# DNVT_box3t.net
KiCad netlist of a schematic drawn in EAGLE
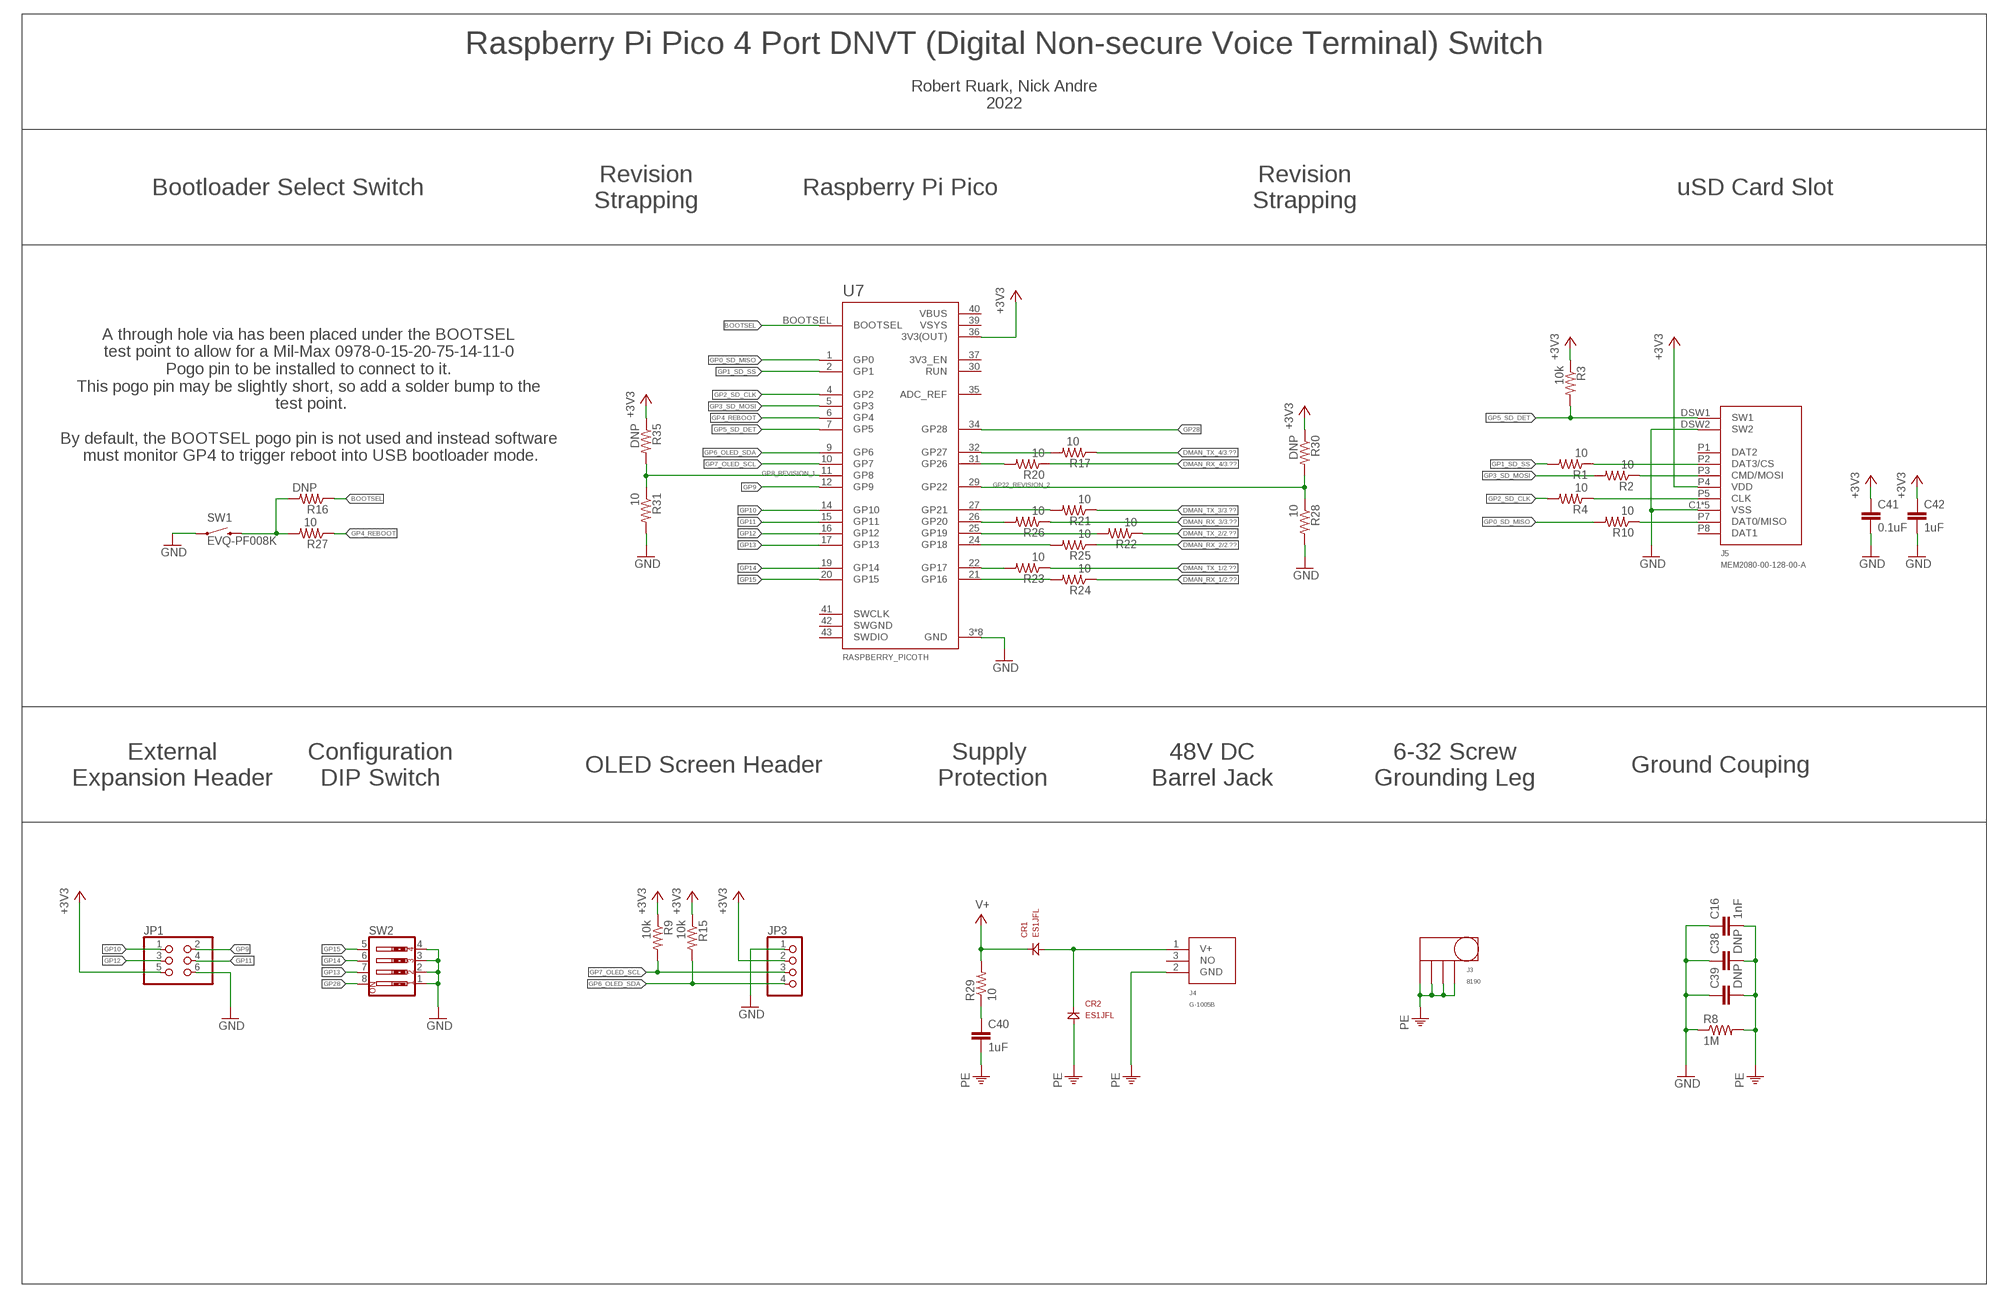
[diagram p0: schematic, sheet 1]
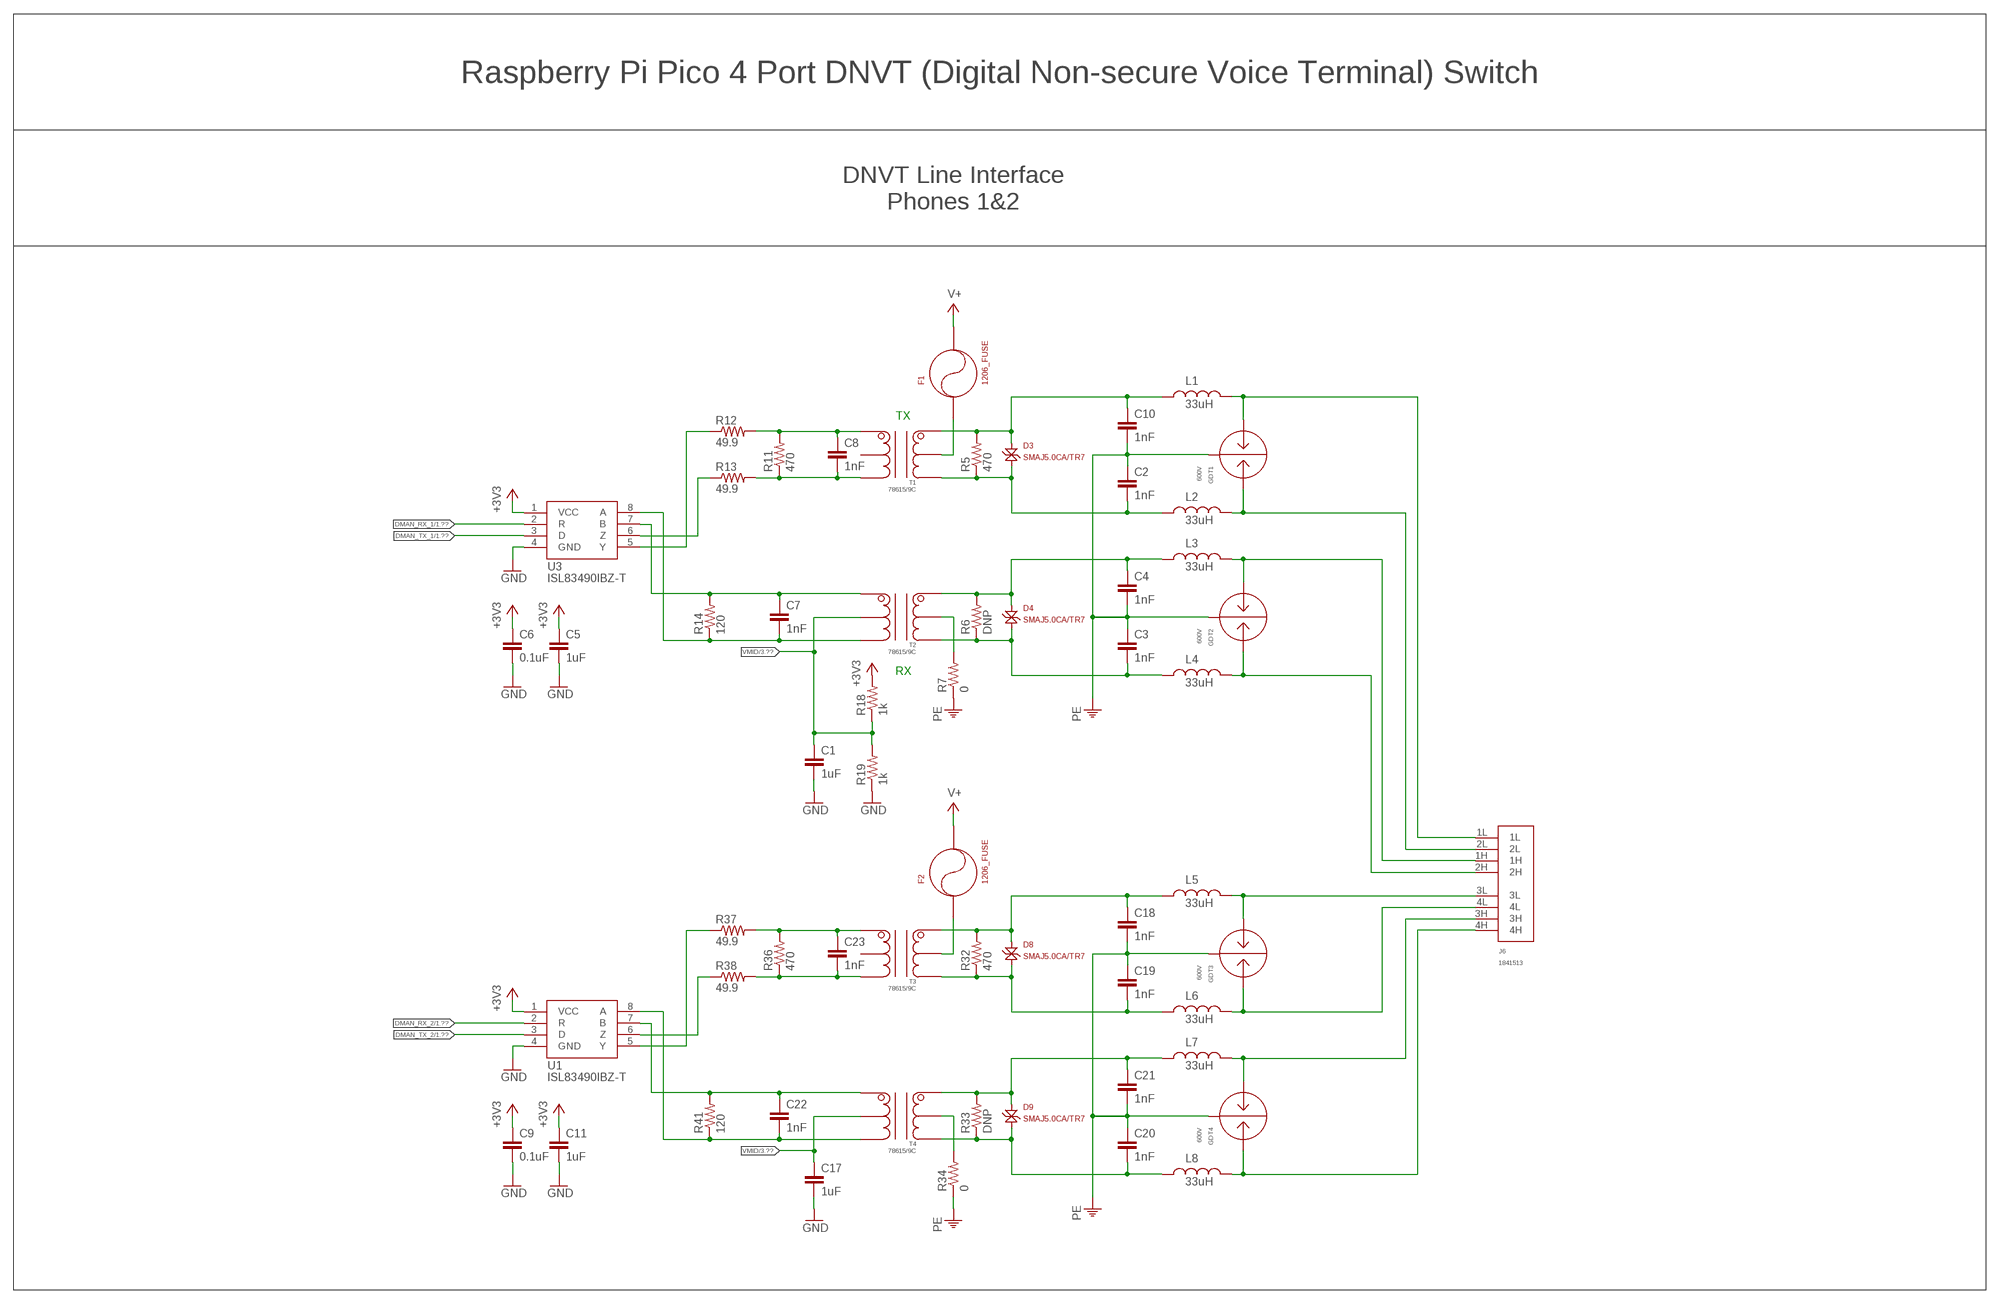
[diagram p1: schematic, sheet 2]
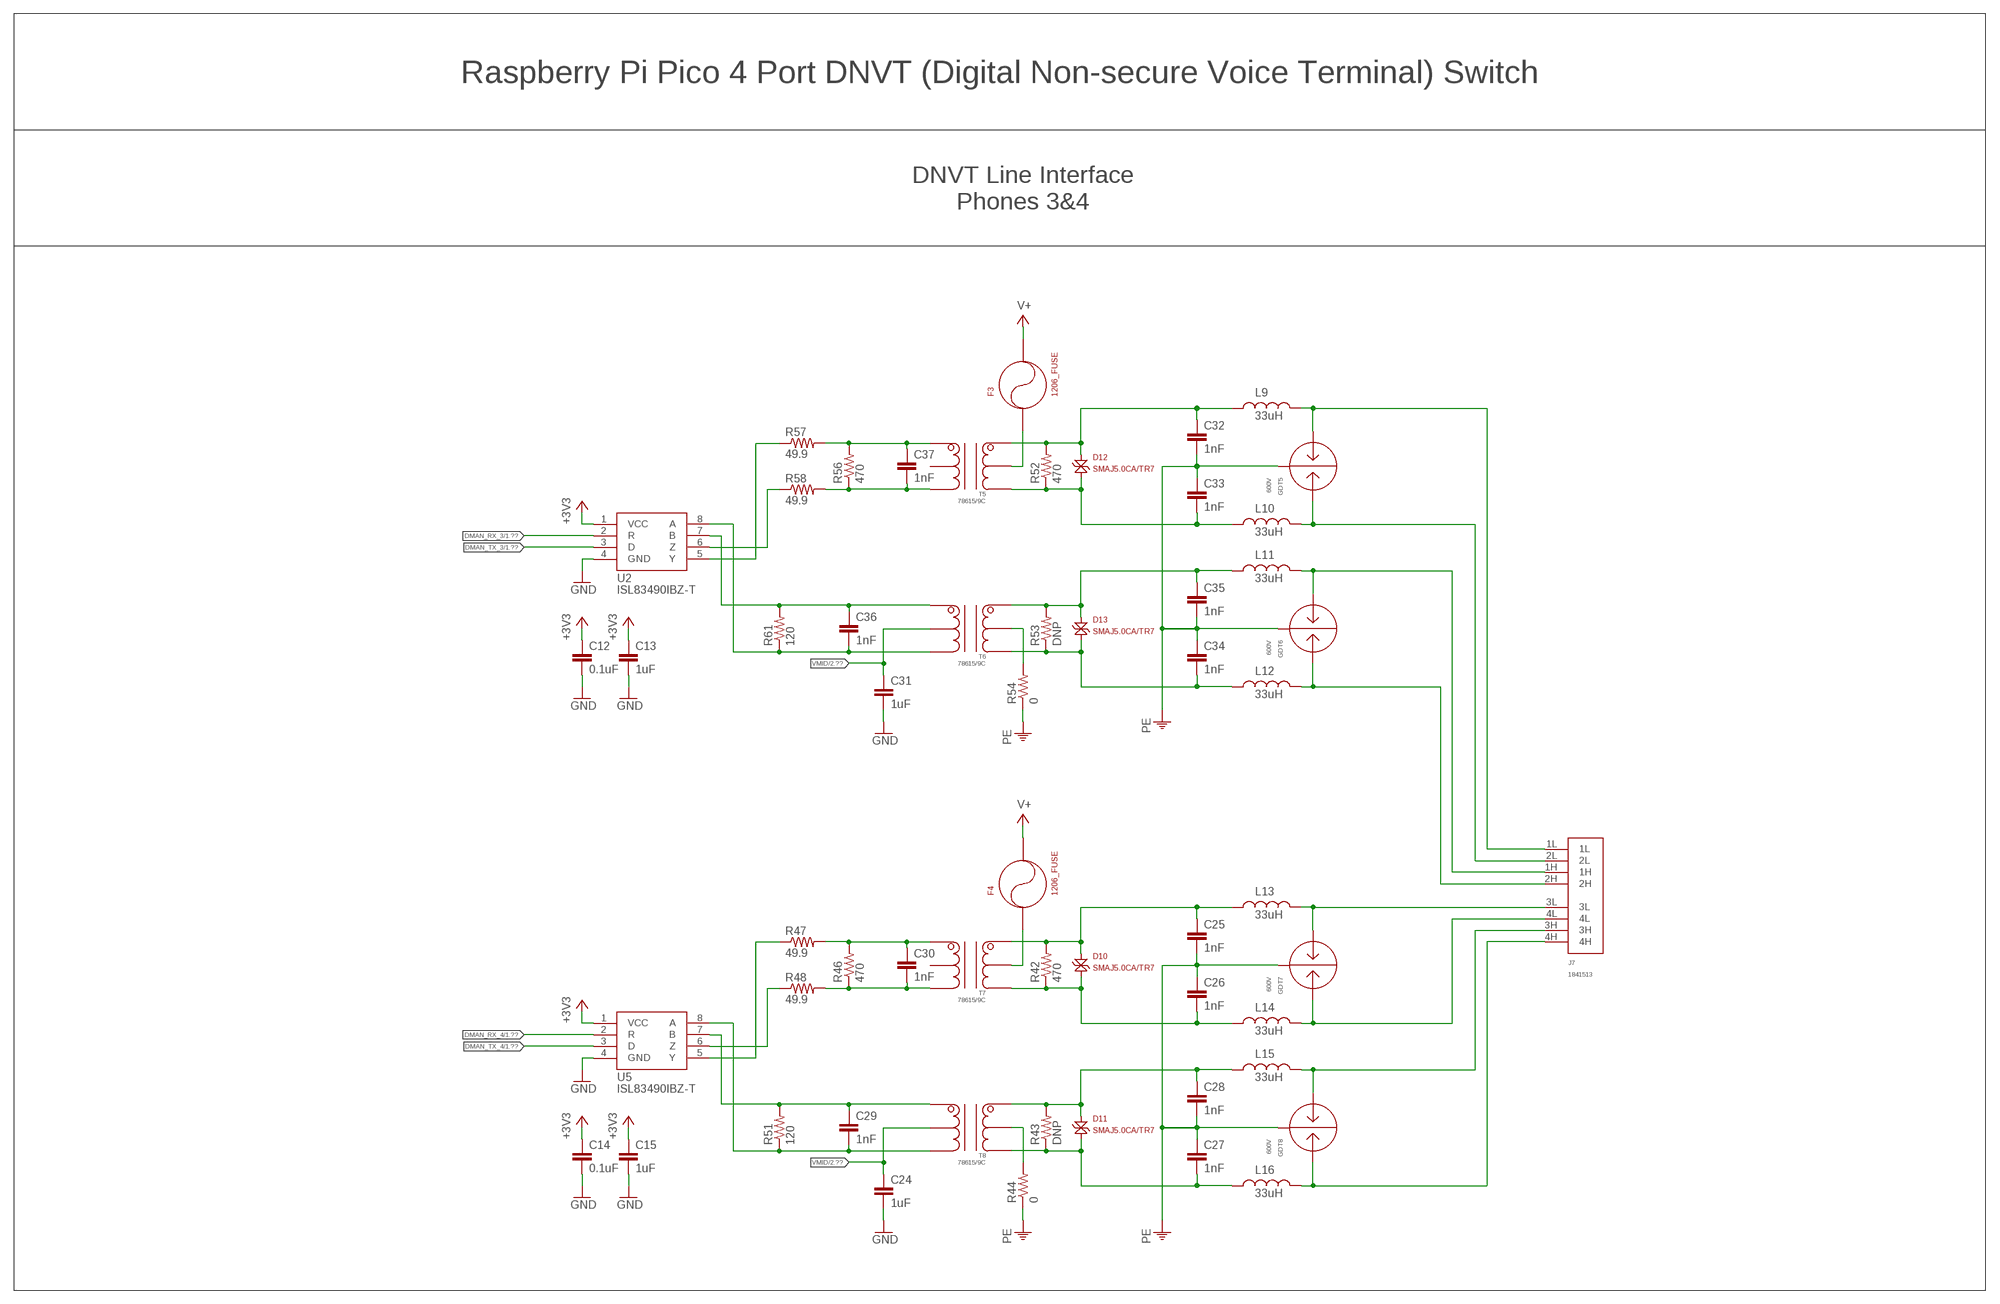
[diagram p2: schematic, sheet 3]

(export (version "E")
  (design (tool "Eeschema 10.0.6"))
  (components
    (comp (ref "C1")
      (value "1uF")
      (footprint "eagle-import:0805")
      (libsource (lib "eagle-import") (part "0805_CAPACITOR"))
    )
    (comp (ref "C2")
      (value "1nF")
      (footprint "eagle-import:0805")
      (libsource (lib "eagle-import") (part "0805_CAPACITOR"))
    )
    (comp (ref "C3")
      (value "1nF")
      (footprint "eagle-import:0805")
      (libsource (lib "eagle-import") (part "0805_CAPACITOR"))
    )
    (comp (ref "C4")
      (value "1nF")
      (footprint "eagle-import:0805")
      (libsource (lib "eagle-import") (part "0805_CAPACITOR"))
    )
    (comp (ref "C5")
      (value "1uF")
      (footprint "eagle-import:0805")
      (libsource (lib "eagle-import") (part "0805_CAPACITOR"))
    )
    (comp (ref "C6")
      (value "0.1uF")
      (footprint "eagle-import:0603")
      (libsource (lib "eagle-import") (part "0603_CAPACITOR"))
    )
    (comp (ref "C7")
      (value "1nF")
      (footprint "eagle-import:0805")
      (libsource (lib "eagle-import") (part "0805_CAPACITOR"))
    )
    (comp (ref "C8")
      (value "1nF")
      (footprint "eagle-import:0805")
      (libsource (lib "eagle-import") (part "0805_CAPACITOR"))
    )
    (comp (ref "C9")
      (value "0.1uF")
      (footprint "eagle-import:0603")
      (libsource (lib "eagle-import") (part "0603_CAPACITOR"))
    )
    (comp (ref "C10")
      (value "1nF")
      (footprint "eagle-import:0805")
      (libsource (lib "eagle-import") (part "0805_CAPACITOR"))
    )
    (comp (ref "C11")
      (value "1uF")
      (footprint "eagle-import:0805")
      (libsource (lib "eagle-import") (part "0805_CAPACITOR"))
    )
    (comp (ref "C17")
      (value "1uF")
      (footprint "eagle-import:0805")
      (libsource (lib "eagle-import") (part "0805_CAPACITOR"))
    )
    (comp (ref "C18")
      (value "1nF")
      (footprint "eagle-import:0805")
      (libsource (lib "eagle-import") (part "0805_CAPACITOR"))
    )
    (comp (ref "C19")
      (value "1nF")
      (footprint "eagle-import:0805")
      (libsource (lib "eagle-import") (part "0805_CAPACITOR"))
    )
    (comp (ref "C20")
      (value "1nF")
      (footprint "eagle-import:0805")
      (libsource (lib "eagle-import") (part "0805_CAPACITOR"))
    )
    (comp (ref "C21")
      (value "1nF")
      (footprint "eagle-import:0805")
      (libsource (lib "eagle-import") (part "0805_CAPACITOR"))
    )
    (comp (ref "C22")
      (value "1nF")
      (footprint "eagle-import:0805")
      (libsource (lib "eagle-import") (part "0805_CAPACITOR"))
    )
    (comp (ref "C23")
      (value "1nF")
      (footprint "eagle-import:0805")
      (libsource (lib "eagle-import") (part "0805_CAPACITOR"))
    )
    (comp (ref "D3")
      (value "SMAJ5.0CA/TR7")
      (footprint "eagle-import:DO-214AC_NO_POL")
      (libsource (lib "eagle-import") (part "SMAJ5.0CA/TR7"))
    )
    (comp (ref "D4")
      (value "SMAJ5.0CA/TR7")
      (footprint "eagle-import:DO-214AC_NO_POL")
      (libsource (lib "eagle-import") (part "SMAJ5.0CA/TR7"))
    )
    (comp (ref "D8")
      (value "SMAJ5.0CA/TR7")
      (footprint "eagle-import:DO-214AC_NO_POL")
      (libsource (lib "eagle-import") (part "SMAJ5.0CA/TR7"))
    )
    (comp (ref "D9")
      (value "SMAJ5.0CA/TR7")
      (footprint "eagle-import:DO-214AC_NO_POL")
      (libsource (lib "eagle-import") (part "SMAJ5.0CA/TR7"))
    )
    (comp (ref "F1")
      (value "1206_FUSE")
      (footprint "eagle-import:1206")
      (libsource (lib "eagle-import") (part "1206_FUSE"))
    )
    (comp (ref "F2")
      (value "1206_FUSE")
      (footprint "eagle-import:1206")
      (libsource (lib "eagle-import") (part "1206_FUSE"))
    )
    (comp (ref "GDT1")
      (value "600V")
      (footprint "eagle-import:2036_GDT")
      (fields (field (name "PARTNO") "2036-60-SM-RPLFCT-ND"))
      (libsource (lib "eagle-import") (part "2036-60-SM-RPLF"))
    )
    (comp (ref "GDT2")
      (value "600V")
      (footprint "eagle-import:2036_GDT")
      (fields (field (name "PARTNO") "2036-60-SM-RPLFCT-ND"))
      (libsource (lib "eagle-import") (part "2036-60-SM-RPLF"))
    )
    (comp (ref "GDT3")
      (value "600V")
      (footprint "eagle-import:2036_GDT")
      (fields (field (name "PARTNO") "2036-60-SM-RPLFCT-ND"))
      (libsource (lib "eagle-import") (part "2036-60-SM-RPLF"))
    )
    (comp (ref "GDT4")
      (value "600V")
      (footprint "eagle-import:2036_GDT")
      (fields (field (name "PARTNO") "2036-60-SM-RPLFCT-ND"))
      (libsource (lib "eagle-import") (part "2036-60-SM-RPLF"))
    )
    (comp (ref "J6")
      (value "1841513")
      (footprint "eagle-import:1841513")
      (fields (field (name "PARTNO") "277-10317-ND"))
      (libsource (lib "eagle-import") (part "1841513"))
    )
    (comp (ref "L1")
      (value "33uH")
      (footprint "eagle-import:SDR0403")
      (fields (field (name "PARTNO") "SDR0403-330KLCT-ND"))
      (libsource (lib "eagle-import") (part "SDR0403-330KL"))
    )
    (comp (ref "L2")
      (value "33uH")
      (footprint "eagle-import:SDR0403")
      (fields (field (name "PARTNO") "SDR0403-330KLCT-ND"))
      (libsource (lib "eagle-import") (part "SDR0403-330KL"))
    )
    (comp (ref "L3")
      (value "33uH")
      (footprint "eagle-import:SDR0403")
      (fields (field (name "PARTNO") "SDR0403-330KLCT-ND"))
      (libsource (lib "eagle-import") (part "SDR0403-330KL"))
    )
    (comp (ref "L4")
      (value "33uH")
      (footprint "eagle-import:SDR0403")
      (fields (field (name "PARTNO") "SDR0403-330KLCT-ND"))
      (libsource (lib "eagle-import") (part "SDR0403-330KL"))
    )
    (comp (ref "L5")
      (value "33uH")
      (footprint "eagle-import:SDR0403")
      (fields (field (name "PARTNO") "SDR0403-330KLCT-ND"))
      (libsource (lib "eagle-import") (part "SDR0403-330KL"))
    )
    (comp (ref "L6")
      (value "33uH")
      (footprint "eagle-import:SDR0403")
      (fields (field (name "PARTNO") "SDR0403-330KLCT-ND"))
      (libsource (lib "eagle-import") (part "SDR0403-330KL"))
    )
    (comp (ref "L7")
      (value "33uH")
      (footprint "eagle-import:SDR0403")
      (fields (field (name "PARTNO") "SDR0403-330KLCT-ND"))
      (libsource (lib "eagle-import") (part "SDR0403-330KL"))
    )
    (comp (ref "L8")
      (value "33uH")
      (footprint "eagle-import:SDR0403")
      (fields (field (name "PARTNO") "SDR0403-330KLCT-ND"))
      (libsource (lib "eagle-import") (part "SDR0403-330KL"))
    )
    (comp (ref "R5")
      (value "470")
      (footprint "eagle-import:R0805")
      (libsource (lib "eagle-import") (part "R-US_R0805"))
    )
    (comp (ref "R6")
      (value "DNP")
      (footprint "eagle-import:R0805")
      (libsource (lib "eagle-import") (part "R-US_R0805"))
    )
    (comp (ref "R7")
      (value "0")
      (footprint "eagle-import:R0805")
      (libsource (lib "eagle-import") (part "R-US_R0805"))
    )
    (comp (ref "R11")
      (value "470")
      (footprint "eagle-import:R0805")
      (libsource (lib "eagle-import") (part "R-US_R0805"))
    )
    (comp (ref "R12")
      (value "49.9")
      (footprint "eagle-import:R0805")
      (libsource (lib "eagle-import") (part "R-US_R0805"))
    )
    (comp (ref "R13")
      (value "49.9")
      (footprint "eagle-import:R0805")
      (libsource (lib "eagle-import") (part "R-US_R0805"))
    )
    (comp (ref "R14")
      (value "120")
      (footprint "eagle-import:1206")
      (libsource (lib "eagle-import") (part "1206_RESISTOR"))
    )
    (comp (ref "R18")
      (value "1k")
      (footprint "eagle-import:0603")
      (libsource (lib "eagle-import") (part "0603_RESISTOR"))
    )
    (comp (ref "R19")
      (value "1k")
      (footprint "eagle-import:0603")
      (libsource (lib "eagle-import") (part "0603_RESISTOR"))
    )
    (comp (ref "R32")
      (value "470")
      (footprint "eagle-import:R0805")
      (libsource (lib "eagle-import") (part "R-US_R0805"))
    )
    (comp (ref "R33")
      (value "DNP")
      (footprint "eagle-import:R0805")
      (libsource (lib "eagle-import") (part "R-US_R0805"))
    )
    (comp (ref "R34")
      (value "0")
      (footprint "eagle-import:R0805")
      (libsource (lib "eagle-import") (part "R-US_R0805"))
    )
    (comp (ref "R36")
      (value "470")
      (footprint "eagle-import:R0805")
      (libsource (lib "eagle-import") (part "R-US_R0805"))
    )
    (comp (ref "R37")
      (value "49.9")
      (footprint "eagle-import:R0805")
      (libsource (lib "eagle-import") (part "R-US_R0805"))
    )
    (comp (ref "R38")
      (value "49.9")
      (footprint "eagle-import:R0805")
      (libsource (lib "eagle-import") (part "R-US_R0805"))
    )
    (comp (ref "R41")
      (value "120")
      (footprint "eagle-import:1206")
      (libsource (lib "eagle-import") (part "1206_RESISTOR"))
    )
    (comp (ref "T1")
      (value "78615/9C")
      (footprint "eagle-import:786T")
      (libsource (lib "eagle-import") (part "78615/9C"))
    )
    (comp (ref "T2")
      (value "78615/9C")
      (footprint "eagle-import:786T")
      (libsource (lib "eagle-import") (part "78615/9C"))
    )
    (comp (ref "T3")
      (value "78615/9C")
      (footprint "eagle-import:786T")
      (libsource (lib "eagle-import") (part "78615/9C"))
    )
    (comp (ref "T4")
      (value "78615/9C")
      (footprint "eagle-import:786T")
      (libsource (lib "eagle-import") (part "78615/9C"))
    )
    (comp (ref "U1")
      (value "ISL83490IBZ-T")
      (footprint "eagle-import:SOIC8")
      (fields (field (name "PARTNO") "ISL83490IBZ-TCT-ND"))
      (libsource (lib "eagle-import") (part "ISL83490IBZ-T"))
    )
    (comp (ref "U3")
      (value "ISL83490IBZ-T")
      (footprint "eagle-import:SOIC8")
      (fields (field (name "PARTNO") "ISL83490IBZ-TCT-ND"))
      (libsource (lib "eagle-import") (part "ISL83490IBZ-T"))
    )
    (comp (ref "C12")
      (value "0.1uF")
      (footprint "eagle-import:0603")
      (libsource (lib "eagle-import") (part "0603_CAPACITOR"))
    )
    (comp (ref "C13")
      (value "1uF")
      (footprint "eagle-import:0805")
      (libsource (lib "eagle-import") (part "0805_CAPACITOR"))
    )
    (comp (ref "C14")
      (value "0.1uF")
      (footprint "eagle-import:0603")
      (libsource (lib "eagle-import") (part "0603_CAPACITOR"))
    )
    (comp (ref "C15")
      (value "1uF")
      (footprint "eagle-import:0805")
      (libsource (lib "eagle-import") (part "0805_CAPACITOR"))
    )
    (comp (ref "C24")
      (value "1uF")
      (footprint "eagle-import:0805")
      (libsource (lib "eagle-import") (part "0805_CAPACITOR"))
    )
    (comp (ref "C25")
      (value "1nF")
      (footprint "eagle-import:0805")
      (libsource (lib "eagle-import") (part "0805_CAPACITOR"))
    )
    (comp (ref "C26")
      (value "1nF")
      (footprint "eagle-import:0805")
      (libsource (lib "eagle-import") (part "0805_CAPACITOR"))
    )
    (comp (ref "C27")
      (value "1nF")
      (footprint "eagle-import:0805")
      (libsource (lib "eagle-import") (part "0805_CAPACITOR"))
    )
    (comp (ref "C28")
      (value "1nF")
      (footprint "eagle-import:0805")
      (libsource (lib "eagle-import") (part "0805_CAPACITOR"))
    )
    (comp (ref "C29")
      (value "1nF")
      (footprint "eagle-import:0805")
      (libsource (lib "eagle-import") (part "0805_CAPACITOR"))
    )
    (comp (ref "C30")
      (value "1nF")
      (footprint "eagle-import:0805")
      (libsource (lib "eagle-import") (part "0805_CAPACITOR"))
    )
    (comp (ref "C31")
      (value "1uF")
      (footprint "eagle-import:0805")
      (libsource (lib "eagle-import") (part "0805_CAPACITOR"))
    )
    (comp (ref "C32")
      (value "1nF")
      (footprint "eagle-import:0805")
      (libsource (lib "eagle-import") (part "0805_CAPACITOR"))
    )
    (comp (ref "C33")
      (value "1nF")
      (footprint "eagle-import:0805")
      (libsource (lib "eagle-import") (part "0805_CAPACITOR"))
    )
    (comp (ref "C34")
      (value "1nF")
      (footprint "eagle-import:0805")
      (libsource (lib "eagle-import") (part "0805_CAPACITOR"))
    )
    (comp (ref "C35")
      (value "1nF")
      (footprint "eagle-import:0805")
      (libsource (lib "eagle-import") (part "0805_CAPACITOR"))
    )
    (comp (ref "C36")
      (value "1nF")
      (footprint "eagle-import:0805")
      (libsource (lib "eagle-import") (part "0805_CAPACITOR"))
    )
    (comp (ref "C37")
      (value "1nF")
      (footprint "eagle-import:0805")
      (libsource (lib "eagle-import") (part "0805_CAPACITOR"))
    )
    (comp (ref "D10")
      (value "SMAJ5.0CA/TR7")
      (footprint "eagle-import:DO-214AC_NO_POL")
      (libsource (lib "eagle-import") (part "SMAJ5.0CA/TR7"))
    )
    (comp (ref "D11")
      (value "SMAJ5.0CA/TR7")
      (footprint "eagle-import:DO-214AC_NO_POL")
      (libsource (lib "eagle-import") (part "SMAJ5.0CA/TR7"))
    )
    (comp (ref "D12")
      (value "SMAJ5.0CA/TR7")
      (footprint "eagle-import:DO-214AC_NO_POL")
      (libsource (lib "eagle-import") (part "SMAJ5.0CA/TR7"))
    )
    (comp (ref "D13")
      (value "SMAJ5.0CA/TR7")
      (footprint "eagle-import:DO-214AC_NO_POL")
      (libsource (lib "eagle-import") (part "SMAJ5.0CA/TR7"))
    )
    (comp (ref "F3")
      (value "1206_FUSE")
      (footprint "eagle-import:1206")
      (libsource (lib "eagle-import") (part "1206_FUSE"))
    )
    (comp (ref "F4")
      (value "1206_FUSE")
      (footprint "eagle-import:1206")
      (libsource (lib "eagle-import") (part "1206_FUSE"))
    )
    (comp (ref "GDT5")
      (value "600V")
      (footprint "eagle-import:2036_GDT")
      (fields (field (name "PARTNO") "2036-60-SM-RPLFCT-ND"))
      (libsource (lib "eagle-import") (part "2036-60-SM-RPLF"))
    )
    (comp (ref "GDT6")
      (value "600V")
      (footprint "eagle-import:2036_GDT")
      (fields (field (name "PARTNO") "2036-60-SM-RPLFCT-ND"))
      (libsource (lib "eagle-import") (part "2036-60-SM-RPLF"))
    )
    (comp (ref "GDT7")
      (value "600V")
      (footprint "eagle-import:2036_GDT")
      (fields (field (name "PARTNO") "2036-60-SM-RPLFCT-ND"))
      (libsource (lib "eagle-import") (part "2036-60-SM-RPLF"))
    )
    (comp (ref "GDT8")
      (value "600V")
      (footprint "eagle-import:2036_GDT")
      (fields (field (name "PARTNO") "2036-60-SM-RPLFCT-ND"))
      (libsource (lib "eagle-import") (part "2036-60-SM-RPLF"))
    )
    (comp (ref "J7")
      (value "1841513")
      (footprint "eagle-import:1841513")
      (fields (field (name "PARTNO") "277-10317-ND"))
      (libsource (lib "eagle-import") (part "1841513"))
    )
    (comp (ref "L9")
      (value "33uH")
      (footprint "eagle-import:SDR0403")
      (fields (field (name "PARTNO") "SDR0403-330KLCT-ND"))
      (libsource (lib "eagle-import") (part "SDR0403-330KL"))
    )
    (comp (ref "L10")
      (value "33uH")
      (footprint "eagle-import:SDR0403")
      (fields (field (name "PARTNO") "SDR0403-330KLCT-ND"))
      (libsource (lib "eagle-import") (part "SDR0403-330KL"))
    )
    (comp (ref "L11")
      (value "33uH")
      (footprint "eagle-import:SDR0403")
      (fields (field (name "PARTNO") "SDR0403-330KLCT-ND"))
      (libsource (lib "eagle-import") (part "SDR0403-330KL"))
    )
    (comp (ref "L12")
      (value "33uH")
      (footprint "eagle-import:SDR0403")
      (fields (field (name "PARTNO") "SDR0403-330KLCT-ND"))
      (libsource (lib "eagle-import") (part "SDR0403-330KL"))
    )
    (comp (ref "L13")
      (value "33uH")
      (footprint "eagle-import:SDR0403")
      (fields (field (name "PARTNO") "SDR0403-330KLCT-ND"))
      (libsource (lib "eagle-import") (part "SDR0403-330KL"))
    )
    (comp (ref "L14")
      (value "33uH")
      (footprint "eagle-import:SDR0403")
      (fields (field (name "PARTNO") "SDR0403-330KLCT-ND"))
      (libsource (lib "eagle-import") (part "SDR0403-330KL"))
    )
    (comp (ref "L15")
      (value "33uH")
      (footprint "eagle-import:SDR0403")
      (fields (field (name "PARTNO") "SDR0403-330KLCT-ND"))
      (libsource (lib "eagle-import") (part "SDR0403-330KL"))
    )
    (comp (ref "L16")
      (value "33uH")
      (footprint "eagle-import:SDR0403")
      (fields (field (name "PARTNO") "SDR0403-330KLCT-ND"))
      (libsource (lib "eagle-import") (part "SDR0403-330KL"))
    )
    (comp (ref "R42")
      (value "470")
      (footprint "eagle-import:R0805")
      (libsource (lib "eagle-import") (part "R-US_R0805"))
    )
    (comp (ref "R43")
      (value "DNP")
      (footprint "eagle-import:R0805")
      (libsource (lib "eagle-import") (part "R-US_R0805"))
    )
    (comp (ref "R44")
      (value "0")
      (footprint "eagle-import:R0805")
      (libsource (lib "eagle-import") (part "R-US_R0805"))
    )
    (comp (ref "R46")
      (value "470")
      (footprint "eagle-import:R0805")
      (libsource (lib "eagle-import") (part "R-US_R0805"))
    )
    (comp (ref "R47")
      (value "49.9")
      (footprint "eagle-import:R0805")
      (libsource (lib "eagle-import") (part "R-US_R0805"))
    )
    (comp (ref "R48")
      (value "49.9")
      (footprint "eagle-import:R0805")
      (libsource (lib "eagle-import") (part "R-US_R0805"))
    )
    (comp (ref "R51")
      (value "120")
      (footprint "eagle-import:1206")
      (libsource (lib "eagle-import") (part "1206_RESISTOR"))
    )
    (comp (ref "R52")
      (value "470")
      (footprint "eagle-import:R0805")
      (libsource (lib "eagle-import") (part "R-US_R0805"))
    )
    (comp (ref "R53")
      (value "DNP")
      (footprint "eagle-import:R0805")
      (libsource (lib "eagle-import") (part "R-US_R0805"))
    )
    (comp (ref "R54")
      (value "0")
      (footprint "eagle-import:R0805")
      (libsource (lib "eagle-import") (part "R-US_R0805"))
    )
    (comp (ref "R56")
      (value "470")
      (footprint "eagle-import:R0805")
      (libsource (lib "eagle-import") (part "R-US_R0805"))
    )
    (comp (ref "R57")
      (value "49.9")
      (footprint "eagle-import:R0805")
      (libsource (lib "eagle-import") (part "R-US_R0805"))
    )
    (comp (ref "R58")
      (value "49.9")
      (footprint "eagle-import:R0805")
      (libsource (lib "eagle-import") (part "R-US_R0805"))
    )
    (comp (ref "R61")
      (value "120")
      (footprint "eagle-import:1206")
      (libsource (lib "eagle-import") (part "1206_RESISTOR"))
    )
    (comp (ref "T5")
      (value "78615/9C")
      (footprint "eagle-import:786T")
      (libsource (lib "eagle-import") (part "78615/9C"))
    )
    (comp (ref "T6")
      (value "78615/9C")
      (footprint "eagle-import:786T")
      (libsource (lib "eagle-import") (part "78615/9C"))
    )
    (comp (ref "T7")
      (value "78615/9C")
      (footprint "eagle-import:786T")
      (libsource (lib "eagle-import") (part "78615/9C"))
    )
    (comp (ref "T8")
      (value "78615/9C")
      (footprint "eagle-import:786T")
      (libsource (lib "eagle-import") (part "78615/9C"))
    )
    (comp (ref "U2")
      (value "ISL83490IBZ-T")
      (footprint "eagle-import:SOIC8")
      (fields (field (name "PARTNO") "ISL83490IBZ-TCT-ND"))
      (libsource (lib "eagle-import") (part "ISL83490IBZ-T"))
    )
    (comp (ref "U5")
      (value "ISL83490IBZ-T")
      (footprint "eagle-import:SOIC8")
      (fields (field (name "PARTNO") "ISL83490IBZ-TCT-ND"))
      (libsource (lib "eagle-import") (part "ISL83490IBZ-T"))
    )
    (comp (ref "C16")
      (value "1nF")
      (footprint "eagle-import:1206")
      (libsource (lib "eagle-import") (part "1206_CAPACITOR"))
    )
    (comp (ref "C38")
      (value "DNP")
      (footprint "eagle-import:1206")
      (libsource (lib "eagle-import") (part "1206_CAPACITOR"))
    )
    (comp (ref "C39")
      (value "DNP")
      (footprint "eagle-import:1206")
      (libsource (lib "eagle-import") (part "1206_CAPACITOR"))
    )
    (comp (ref "C40")
      (value "1uF")
      (footprint "eagle-import:1206")
      (libsource (lib "eagle-import") (part "1206_CAPACITOR"))
    )
    (comp (ref "C41")
      (value "0.1uF")
      (footprint "eagle-import:0603")
      (libsource (lib "eagle-import") (part "0603_CAPACITOR"))
    )
    (comp (ref "C42")
      (value "1uF")
      (footprint "eagle-import:0805")
      (libsource (lib "eagle-import") (part "0805_CAPACITOR"))
    )
    (comp (ref "CR1")
      (value "ES1JFL")
      (footprint "eagle-import:SOD123(AK)")
      (fields (field (name "PARTNO") "ES1JFLCT-ND"))
      (libsource (lib "eagle-import") (part "ES1JFL"))
    )
    (comp (ref "CR2")
      (value "ES1JFL")
      (footprint "eagle-import:SOD123(AK)")
      (fields (field (name "PARTNO") "ES1JFLCT-ND"))
      (libsource (lib "eagle-import") (part "ES1JFL"))
    )
    (comp (ref "J3")
      (value "8190")
      (footprint "eagle-import:7781")
      (fields (field (name "PARTNO") "36-8190-ND"))
      (libsource (lib "eagle-import") (part "8190"))
    )
    (comp (ref "J4")
      (value "G-1005B")
      (footprint "eagle-import:G-1005B")
      (fields (field (name "PARTNO") "1939-G-1005B-ND"))
      (libsource (lib "eagle-import") (part "G-1005B"))
    )
    (comp (ref "J5")
      (value "MEM2080-00-128-00-A")
      (footprint "eagle-import:MEM2080")
      (fields (field (name "PARTNO") "2073-MEM2080-00-128-00-ACT-ND"))
      (libsource (lib "eagle-import") (part "MEM2080-00-128-00-A"))
    )
    (comp (ref "JP1")
      (value "PINHD-2X3/90")
      (footprint "eagle-import:2X03_90")
      (libsource (lib "eagle-import") (part "PINHD-2X3/90"))
    )
    (comp (ref "JP3")
      (value "PINHD-1X4")
      (footprint "eagle-import:1X04")
      (libsource (lib "eagle-import") (part "PINHD-1X4"))
    )
    (comp (ref "R1")
      (value "10")
      (footprint "eagle-import:0603")
      (libsource (lib "eagle-import") (part "0603_RESISTOR"))
    )
    (comp (ref "R2")
      (value "10")
      (footprint "eagle-import:0603")
      (libsource (lib "eagle-import") (part "0603_RESISTOR"))
    )
    (comp (ref "R3")
      (value "10k")
      (footprint "eagle-import:0603")
      (libsource (lib "eagle-import") (part "0603_RESISTOR"))
    )
    (comp (ref "R4")
      (value "10")
      (footprint "eagle-import:0603")
      (libsource (lib "eagle-import") (part "0603_RESISTOR"))
    )
    (comp (ref "R8")
      (value "1M")
      (footprint "eagle-import:1206")
      (libsource (lib "eagle-import") (part "1206_RESISTOR"))
    )
    (comp (ref "R9")
      (value "10k")
      (footprint "eagle-import:0603")
      (libsource (lib "eagle-import") (part "0603_RESISTOR"))
    )
    (comp (ref "R10")
      (value "10")
      (footprint "eagle-import:0603")
      (libsource (lib "eagle-import") (part "0603_RESISTOR"))
    )
    (comp (ref "R15")
      (value "10k")
      (footprint "eagle-import:0603")
      (libsource (lib "eagle-import") (part "0603_RESISTOR"))
    )
    (comp (ref "R16")
      (value "DNP")
      (footprint "eagle-import:0603")
      (libsource (lib "eagle-import") (part "0603_RESISTOR"))
    )
    (comp (ref "R17")
      (value "10")
      (footprint "eagle-import:0603")
      (libsource (lib "eagle-import") (part "0603_RESISTOR"))
    )
    (comp (ref "R20")
      (value "10")
      (footprint "eagle-import:0603")
      (libsource (lib "eagle-import") (part "0603_RESISTOR"))
    )
    (comp (ref "R21")
      (value "10")
      (footprint "eagle-import:0603")
      (libsource (lib "eagle-import") (part "0603_RESISTOR"))
    )
    (comp (ref "R22")
      (value "10")
      (footprint "eagle-import:0603")
      (libsource (lib "eagle-import") (part "0603_RESISTOR"))
    )
    (comp (ref "R23")
      (value "10")
      (footprint "eagle-import:0603")
      (libsource (lib "eagle-import") (part "0603_RESISTOR"))
    )
    (comp (ref "R24")
      (value "10")
      (footprint "eagle-import:0603")
      (libsource (lib "eagle-import") (part "0603_RESISTOR"))
    )
    (comp (ref "R25")
      (value "10")
      (footprint "eagle-import:0603")
      (libsource (lib "eagle-import") (part "0603_RESISTOR"))
    )
    (comp (ref "R26")
      (value "10")
      (footprint "eagle-import:0603")
      (libsource (lib "eagle-import") (part "0603_RESISTOR"))
    )
    (comp (ref "R27")
      (value "10")
      (footprint "eagle-import:0603")
      (libsource (lib "eagle-import") (part "0603_RESISTOR"))
    )
    (comp (ref "R28")
      (value "10")
      (footprint "eagle-import:0603")
      (libsource (lib "eagle-import") (part "0603_RESISTOR"))
    )
    (comp (ref "R29")
      (value "10")
      (footprint "eagle-import:1206")
      (libsource (lib "eagle-import") (part "1206_RESISTOR"))
    )
    (comp (ref "R30")
      (value "DNP")
      (footprint "eagle-import:0603")
      (libsource (lib "eagle-import") (part "0603_RESISTOR"))
    )
    (comp (ref "R31")
      (value "10")
      (footprint "eagle-import:0603")
      (libsource (lib "eagle-import") (part "0603_RESISTOR"))
    )
    (comp (ref "R35")
      (value "DNP")
      (footprint "eagle-import:0603")
      (libsource (lib "eagle-import") (part "0603_RESISTOR"))
    )
    (comp (ref "SW1")
      (value "EVQ-PF008K")
      (footprint "eagle-import:EVQ-PF008K")
      (fields (field (name "PARTNO") "P10880S-ND"))
      (libsource (lib "eagle-import") (part "EVQ-PF008K"))
    )
    (comp (ref "SW2")
      (value "SW_DIP-4")
      (footprint "eagle-import:EDG-04")
      (libsource (lib "eagle-import") (part "SW_DIP-4"))
    )
    (comp (ref "U7")
      (value "RASPBERRY_PICOTH")
      (footprint "eagle-import:PICO-PKG-TH")
      (libsource (lib "eagle-import") (part "RASPBERRY_PICOTH"))
    )
  )
  (nets
    (net (code "1") (name "+3V3") (class "Default")
      (node (ref "C11") (pin "1") (pinfunction "1_1") (pintype "passive"))
      (node (ref "C12") (pin "1") (pinfunction "1_1") (pintype "passive"))
      (node (ref "C13") (pin "1") (pinfunction "1_1") (pintype "passive"))
      (node (ref "C14") (pin "1") (pinfunction "1_1") (pintype "passive"))
      (node (ref "C15") (pin "1") (pinfunction "1_1") (pintype "passive"))
      (node (ref "C41") (pin "1") (pinfunction "1_1") (pintype "passive"))
      (node (ref "C42") (pin "1") (pinfunction "1_1") (pintype "passive"))
      (node (ref "C5") (pin "1") (pinfunction "1_1") (pintype "passive"))
      (node (ref "C6") (pin "1") (pinfunction "1_1") (pintype "passive"))
      (node (ref "C9") (pin "1") (pinfunction "1_1") (pintype "passive"))
      (node (ref "J5") (pin "P4") (pinfunction "VDD_P4") (pintype "bidirectional"))
      (node (ref "JP1") (pin "5") (pinfunction "5_5") (pintype "passive"))
      (node (ref "JP3") (pin "2") (pinfunction "2_2") (pintype "passive"))
      (node (ref "R15") (pin "1") (pinfunction "1_1") (pintype "passive"))
      (node (ref "R18") (pin "2") (pinfunction "2_2") (pintype "passive"))
      (node (ref "R3") (pin "1") (pinfunction "1_1") (pintype "passive"))
      (node (ref "R30") (pin "1") (pinfunction "1_1") (pintype "passive"))
      (node (ref "R35") (pin "1") (pinfunction "1_1") (pintype "passive"))
      (node (ref "R9") (pin "1") (pinfunction "1_1") (pintype "passive"))
      (node (ref "U1") (pin "1") (pinfunction "VCC_1") (pintype "bidirectional"))
      (node (ref "U2") (pin "1") (pinfunction "VCC_1") (pintype "bidirectional"))
      (node (ref "U3") (pin "1") (pinfunction "VCC_1") (pintype "bidirectional"))
      (node (ref "U5") (pin "1") (pinfunction "VCC_1") (pintype "bidirectional"))
      (node (ref "U7") (pin "36") (pinfunction "3V3(OUT)_36") (pintype "power_in"))
    )
    (net (code "2") (name "BOOTSEL") (class "Default")
      (node (ref "R16") (pin "1") (pinfunction "1_1") (pintype "passive"))
      (node (ref "U7") (pin "BOOTSEL") (pinfunction "BOOTSEL_BOOTSEL") (pintype "bidirectional"))
    )
    (net (code "3") (name "DMAN_RX_1") (class "Default")
      (node (ref "R24") (pin "1") (pinfunction "1_1") (pintype "passive"))
      (node (ref "U3") (pin "2") (pinfunction "R_2") (pintype "bidirectional"))
    )
    (net (code "4") (name "DMAN_RX_2") (class "Default")
      (node (ref "R25") (pin "1") (pinfunction "1_1") (pintype "passive"))
      (node (ref "U1") (pin "2") (pinfunction "R_2") (pintype "bidirectional"))
    )
    (net (code "5") (name "DMAN_RX_3") (class "Default")
      (node (ref "R26") (pin "1") (pinfunction "1_1") (pintype "passive"))
      (node (ref "U2") (pin "2") (pinfunction "R_2") (pintype "bidirectional"))
    )
    (net (code "6") (name "DMAN_RX_4") (class "Default")
      (node (ref "R20") (pin "1") (pinfunction "1_1") (pintype "passive"))
      (node (ref "U5") (pin "2") (pinfunction "R_2") (pintype "bidirectional"))
    )
    (net (code "7") (name "DMAN_TX_1") (class "Default")
      (node (ref "R23") (pin "1") (pinfunction "1_1") (pintype "passive"))
      (node (ref "U3") (pin "3") (pinfunction "D_3") (pintype "bidirectional"))
    )
    (net (code "8") (name "DMAN_TX_2") (class "Default")
      (node (ref "R22") (pin "1") (pinfunction "1_1") (pintype "passive"))
      (node (ref "U1") (pin "3") (pinfunction "D_3") (pintype "bidirectional"))
    )
    (net (code "9") (name "DMAN_TX_3") (class "Default")
      (node (ref "R21") (pin "1") (pinfunction "1_1") (pintype "passive"))
      (node (ref "U2") (pin "3") (pinfunction "D_3") (pintype "bidirectional"))
    )
    (net (code "10") (name "DMAN_TX_4") (class "Default")
      (node (ref "R17") (pin "1") (pinfunction "1_1") (pintype "passive"))
      (node (ref "U5") (pin "3") (pinfunction "D_3") (pintype "bidirectional"))
    )
    (net (code "11") (name "GND") (class "Default")
      (node (ref "C1") (pin "2") (pinfunction "2_2") (pintype "passive"))
      (node (ref "C11") (pin "2") (pinfunction "2_2") (pintype "passive"))
      (node (ref "C12") (pin "2") (pinfunction "2_2") (pintype "passive"))
      (node (ref "C13") (pin "2") (pinfunction "2_2") (pintype "passive"))
      (node (ref "C14") (pin "2") (pinfunction "2_2") (pintype "passive"))
      (node (ref "C15") (pin "2") (pinfunction "2_2") (pintype "passive"))
      (node (ref "C16") (pin "1") (pinfunction "1_1") (pintype "passive"))
      (node (ref "C17") (pin "2") (pinfunction "2_2") (pintype "passive"))
      (node (ref "C24") (pin "2") (pinfunction "2_2") (pintype "passive"))
      (node (ref "C31") (pin "2") (pinfunction "2_2") (pintype "passive"))
      (node (ref "C38") (pin "1") (pinfunction "1_1") (pintype "passive"))
      (node (ref "C39") (pin "1") (pinfunction "1_1") (pintype "passive"))
      (node (ref "C41") (pin "2") (pinfunction "2_2") (pintype "passive"))
      (node (ref "C42") (pin "2") (pinfunction "2_2") (pintype "passive"))
      (node (ref "C5") (pin "2") (pinfunction "2_2") (pintype "passive"))
      (node (ref "C6") (pin "2") (pinfunction "2_2") (pintype "passive"))
      (node (ref "C9") (pin "2") (pinfunction "2_2") (pintype "passive"))
      (node (ref "J5") (pin "C1") (pinfunction "VSS_C1") (pintype "bidirectional"))
      (node (ref "J5") (pin "C2") (pinfunction "VSS_C2") (pintype "bidirectional"))
      (node (ref "J5") (pin "C3") (pinfunction "VSS_C3") (pintype "bidirectional"))
      (node (ref "J5") (pin "C4") (pinfunction "VSS_C4") (pintype "bidirectional"))
      (node (ref "J5") (pin "DSW2") (pinfunction "SW2_DSW2") (pintype "bidirectional"))
      (node (ref "J5") (pin "P6") (pinfunction "VSS_P6") (pintype "bidirectional"))
      (node (ref "JP1") (pin "6") (pinfunction "6_6") (pintype "passive"))
      (node (ref "JP3") (pin "1") (pinfunction "1_1") (pintype "passive"))
      (node (ref "R19") (pin "1") (pinfunction "1_1") (pintype "passive"))
      (node (ref "R28") (pin "2") (pinfunction "2_2") (pintype "passive"))
      (node (ref "R31") (pin "2") (pinfunction "2_2") (pintype "passive"))
      (node (ref "R8") (pin "1") (pinfunction "1_1") (pintype "passive"))
      (node (ref "SW1") (pin "S1") (pinfunction "1_S1") (pintype "passive"))
      (node (ref "SW2") (pin "1") (pinfunction "1_1") (pintype "passive"))
      (node (ref "SW2") (pin "2") (pinfunction "2_2") (pintype "passive"))
      (node (ref "SW2") (pin "3") (pinfunction "3_3") (pintype "passive"))
      (node (ref "SW2") (pin "4") (pinfunction "4_4") (pintype "passive"))
      (node (ref "U1") (pin "4") (pinfunction "GND_4") (pintype "bidirectional"))
      (node (ref "U2") (pin "4") (pinfunction "GND_4") (pintype "bidirectional"))
      (node (ref "U3") (pin "4") (pinfunction "GND_4") (pintype "bidirectional"))
      (node (ref "U5") (pin "4") (pinfunction "GND_4") (pintype "bidirectional"))
      (node (ref "U7") (pin "13") (pinfunction "GND_13") (pintype "power_in"))
      (node (ref "U7") (pin "18") (pinfunction "GND_18") (pintype "power_in"))
      (node (ref "U7") (pin "23") (pinfunction "GND_23") (pintype "power_in"))
      (node (ref "U7") (pin "28") (pinfunction "GND_28") (pintype "power_in"))
      (node (ref "U7") (pin "3") (pinfunction "GND_3") (pintype "power_in"))
      (node (ref "U7") (pin "33") (pinfunction "GND_33") (pintype "power_in"))
      (node (ref "U7") (pin "38") (pinfunction "GND_38") (pintype "power_in"))
      (node (ref "U7") (pin "8") (pinfunction "GND_8") (pintype "power_in"))
    )
    (net (code "12") (name "GP0_SD_MISO") (class "Default")
      (node (ref "R10") (pin "2") (pinfunction "2_2") (pintype "passive"))
      (node (ref "U7") (pin "1") (pinfunction "GP0_1") (pintype "bidirectional"))
    )
    (net (code "13") (name "GP1_SD_SS") (class "Default")
      (node (ref "R1") (pin "2") (pinfunction "2_2") (pintype "passive"))
      (node (ref "U7") (pin "2") (pinfunction "GP1_2") (pintype "bidirectional"))
    )
    (net (code "14") (name "GP2_SD_CLK") (class "Default")
      (node (ref "R4") (pin "2") (pinfunction "2_2") (pintype "passive"))
      (node (ref "U7") (pin "4") (pinfunction "GP2_4") (pintype "bidirectional"))
    )
    (net (code "15") (name "GP3_SD_MOSI") (class "Default")
      (node (ref "R2") (pin "2") (pinfunction "2_2") (pintype "passive"))
      (node (ref "U7") (pin "5") (pinfunction "GP3_5") (pintype "bidirectional"))
    )
    (net (code "16") (name "GP4_REBOOT") (class "Default")
      (node (ref "R27") (pin "1") (pinfunction "1_1") (pintype "passive"))
      (node (ref "U7") (pin "6") (pinfunction "GP4_6") (pintype "bidirectional"))
    )
    (net (code "17") (name "GP5_SD_DET") (class "Default")
      (node (ref "J5") (pin "DSW1") (pinfunction "SW1_DSW1") (pintype "bidirectional"))
      (node (ref "R3") (pin "2") (pinfunction "2_2") (pintype "passive"))
      (node (ref "U7") (pin "7") (pinfunction "GP5_7") (pintype "bidirectional"))
    )
    (net (code "18") (name "GP6_OLED_SDA") (class "Default")
      (node (ref "JP3") (pin "4") (pinfunction "4_4") (pintype "passive"))
      (node (ref "R15") (pin "2") (pinfunction "2_2") (pintype "passive"))
      (node (ref "U7") (pin "9") (pinfunction "GP6_9") (pintype "bidirectional"))
    )
    (net (code "19") (name "GP7_OLED_SCL") (class "Default")
      (node (ref "JP3") (pin "3") (pinfunction "3_3") (pintype "passive"))
      (node (ref "R9") (pin "2") (pinfunction "2_2") (pintype "passive"))
      (node (ref "U7") (pin "10") (pinfunction "GP7_10") (pintype "bidirectional"))
    )
    (net (code "20") (name "GP8_REVISION_1") (class "Default")
      (node (ref "R31") (pin "1") (pinfunction "1_1") (pintype "passive"))
      (node (ref "R35") (pin "2") (pinfunction "2_2") (pintype "passive"))
      (node (ref "U7") (pin "11") (pinfunction "GP8_11") (pintype "bidirectional"))
    )
    (net (code "21") (name "GP9") (class "Default")
      (node (ref "JP1") (pin "2") (pinfunction "2_2") (pintype "passive"))
      (node (ref "U7") (pin "12") (pinfunction "GP9_12") (pintype "bidirectional"))
    )
    (net (code "22") (name "GP10") (class "Default")
      (node (ref "JP1") (pin "1") (pinfunction "1_1") (pintype "passive"))
      (node (ref "U7") (pin "14") (pinfunction "GP10_14") (pintype "bidirectional"))
    )
    (net (code "23") (name "GP11") (class "Default")
      (node (ref "JP1") (pin "4") (pinfunction "4_4") (pintype "passive"))
      (node (ref "U7") (pin "15") (pinfunction "GP11_15") (pintype "bidirectional"))
    )
    (net (code "24") (name "GP12") (class "Default")
      (node (ref "JP1") (pin "3") (pinfunction "3_3") (pintype "passive"))
      (node (ref "U7") (pin "16") (pinfunction "GP12_16") (pintype "bidirectional"))
    )
    (net (code "25") (name "GP13") (class "Default")
      (node (ref "SW2") (pin "7") (pinfunction "7_7") (pintype "passive"))
      (node (ref "U7") (pin "17") (pinfunction "GP13_17") (pintype "bidirectional"))
    )
    (net (code "26") (name "GP14") (class "Default")
      (node (ref "SW2") (pin "6") (pinfunction "6_6") (pintype "passive"))
      (node (ref "U7") (pin "19") (pinfunction "GP14_19") (pintype "bidirectional"))
    )
    (net (code "27") (name "GP15") (class "Default")
      (node (ref "SW2") (pin "5") (pinfunction "5_5") (pintype "passive"))
      (node (ref "U7") (pin "20") (pinfunction "GP15_20") (pintype "bidirectional"))
    )
    (net (code "28") (name "GP22_REVISION_2") (class "Default")
      (node (ref "R28") (pin "1") (pinfunction "1_1") (pintype "passive"))
      (node (ref "R30") (pin "2") (pinfunction "2_2") (pintype "passive"))
      (node (ref "U7") (pin "29") (pinfunction "GP22_29") (pintype "bidirectional"))
    )
    (net (code "29") (name "GP28") (class "Default")
      (node (ref "SW2") (pin "8") (pinfunction "8_8") (pintype "passive"))
      (node (ref "U7") (pin "34") (pinfunction "GP28_34") (pintype "bidirectional"))
    )
    (net (code "30") (name "Net-(C8-Pad1)") (class "Default")
      (node (ref "C8") (pin "1") (pinfunction "1_1") (pintype "passive"))
      (node (ref "R11") (pin "2") (pinfunction "2_2") (pintype "passive"))
      (node (ref "R12") (pin "2") (pinfunction "2_2") (pintype "passive"))
      (node (ref "T1") (pin "6") (pinfunction "6_6") (pintype "bidirectional"))
    )
    (net (code "31") (name "Net-(C8-Pad2)") (class "Default")
      (node (ref "C8") (pin "2") (pinfunction "2_2") (pintype "passive"))
      (node (ref "R11") (pin "1") (pinfunction "1_1") (pintype "passive"))
      (node (ref "R13") (pin "2") (pinfunction "2_2") (pintype "passive"))
      (node (ref "T1") (pin "4") (pinfunction "4_4") (pintype "bidirectional"))
    )
    (net (code "32") (name "Net-(C23-Pad1)") (class "Default")
      (node (ref "C23") (pin "1") (pinfunction "1_1") (pintype "passive"))
      (node (ref "R36") (pin "2") (pinfunction "2_2") (pintype "passive"))
      (node (ref "R37") (pin "2") (pinfunction "2_2") (pintype "passive"))
      (node (ref "T3") (pin "6") (pinfunction "6_6") (pintype "bidirectional"))
    )
    (net (code "33") (name "Net-(C23-Pad2)") (class "Default")
      (node (ref "C23") (pin "2") (pinfunction "2_2") (pintype "passive"))
      (node (ref "R36") (pin "1") (pinfunction "1_1") (pintype "passive"))
      (node (ref "R38") (pin "2") (pinfunction "2_2") (pintype "passive"))
      (node (ref "T3") (pin "4") (pinfunction "4_4") (pintype "bidirectional"))
    )
    (net (code "34") (name "Net-(C30-Pad1)") (class "Default")
      (node (ref "C30") (pin "1") (pinfunction "1_1") (pintype "passive"))
      (node (ref "R46") (pin "2") (pinfunction "2_2") (pintype "passive"))
      (node (ref "R47") (pin "2") (pinfunction "2_2") (pintype "passive"))
      (node (ref "T7") (pin "6") (pinfunction "6_6") (pintype "bidirectional"))
    )
    (net (code "35") (name "Net-(C30-Pad2)") (class "Default")
      (node (ref "C30") (pin "2") (pinfunction "2_2") (pintype "passive"))
      (node (ref "R46") (pin "1") (pinfunction "1_1") (pintype "passive"))
      (node (ref "R48") (pin "2") (pinfunction "2_2") (pintype "passive"))
      (node (ref "T7") (pin "4") (pinfunction "4_4") (pintype "bidirectional"))
    )
    (net (code "36") (name "Net-(C37-Pad1)") (class "Default")
      (node (ref "C37") (pin "1") (pinfunction "1_1") (pintype "passive"))
      (node (ref "R56") (pin "2") (pinfunction "2_2") (pintype "passive"))
      (node (ref "R57") (pin "2") (pinfunction "2_2") (pintype "passive"))
      (node (ref "T5") (pin "6") (pinfunction "6_6") (pintype "bidirectional"))
    )
    (net (code "37") (name "Net-(C37-Pad2)") (class "Default")
      (node (ref "C37") (pin "2") (pinfunction "2_2") (pintype "passive"))
      (node (ref "R56") (pin "1") (pinfunction "1_1") (pintype "passive"))
      (node (ref "R58") (pin "2") (pinfunction "2_2") (pintype "passive"))
      (node (ref "T5") (pin "4") (pinfunction "4_4") (pintype "bidirectional"))
    )
    (net (code "38") (name "Net-(C40-Pad1)") (class "Default")
      (node (ref "C40") (pin "1") (pinfunction "1_1") (pintype "passive"))
      (node (ref "R29") (pin "1") (pinfunction "1_1") (pintype "passive"))
    )
    (net (code "39") (name "Net-(D3-K)") (class "Default")
      (node (ref "C10") (pin "1") (pinfunction "1_1") (pintype "passive"))
      (node (ref "D3") (pin "C") (pinfunction "K_C") (pintype "bidirectional"))
      (node (ref "L1") (pin "1") (pinfunction "P$1_1") (pintype "bidirectional"))
      (node (ref "R5") (pin "2") (pinfunction "2_2") (pintype "passive"))
      (node (ref "T1") (pin "1") (pinfunction "1_1") (pintype "bidirectional"))
    )
    (net (code "40") (name "Net-(D4-K)") (class "Default")
      (node (ref "C4") (pin "1") (pinfunction "1_1") (pintype "passive"))
      (node (ref "D4") (pin "C") (pinfunction "K_C") (pintype "bidirectional"))
      (node (ref "L3") (pin "1") (pinfunction "P$1_1") (pintype "bidirectional"))
      (node (ref "R6") (pin "2") (pinfunction "2_2") (pintype "passive"))
      (node (ref "T2") (pin "1") (pinfunction "1_1") (pintype "bidirectional"))
    )
    (net (code "41") (name "Net-(D8-K)") (class "Default")
      (node (ref "C18") (pin "1") (pinfunction "1_1") (pintype "passive"))
      (node (ref "D8") (pin "C") (pinfunction "K_C") (pintype "bidirectional"))
      (node (ref "L5") (pin "1") (pinfunction "P$1_1") (pintype "bidirectional"))
      (node (ref "R32") (pin "2") (pinfunction "2_2") (pintype "passive"))
      (node (ref "T3") (pin "1") (pinfunction "1_1") (pintype "bidirectional"))
    )
    (net (code "42") (name "Net-(D9-K)") (class "Default")
      (node (ref "C21") (pin "1") (pinfunction "1_1") (pintype "passive"))
      (node (ref "D9") (pin "C") (pinfunction "K_C") (pintype "bidirectional"))
      (node (ref "L7") (pin "1") (pinfunction "P$1_1") (pintype "bidirectional"))
      (node (ref "R33") (pin "2") (pinfunction "2_2") (pintype "passive"))
      (node (ref "T4") (pin "1") (pinfunction "1_1") (pintype "bidirectional"))
    )
    (net (code "43") (name "Net-(D10-K)") (class "Default")
      (node (ref "C25") (pin "1") (pinfunction "1_1") (pintype "passive"))
      (node (ref "D10") (pin "C") (pinfunction "K_C") (pintype "bidirectional"))
      (node (ref "L13") (pin "1") (pinfunction "P$1_1") (pintype "bidirectional"))
      (node (ref "R42") (pin "2") (pinfunction "2_2") (pintype "passive"))
      (node (ref "T7") (pin "1") (pinfunction "1_1") (pintype "bidirectional"))
    )
    (net (code "44") (name "Net-(D11-K)") (class "Default")
      (node (ref "C28") (pin "1") (pinfunction "1_1") (pintype "passive"))
      (node (ref "D11") (pin "C") (pinfunction "K_C") (pintype "bidirectional"))
      (node (ref "L15") (pin "1") (pinfunction "P$1_1") (pintype "bidirectional"))
      (node (ref "R43") (pin "2") (pinfunction "2_2") (pintype "passive"))
      (node (ref "T8") (pin "1") (pinfunction "1_1") (pintype "bidirectional"))
    )
    (net (code "45") (name "Net-(D12-K)") (class "Default")
      (node (ref "C32") (pin "1") (pinfunction "1_1") (pintype "passive"))
      (node (ref "D12") (pin "C") (pinfunction "K_C") (pintype "bidirectional"))
      (node (ref "L9") (pin "1") (pinfunction "P$1_1") (pintype "bidirectional"))
      (node (ref "R52") (pin "2") (pinfunction "2_2") (pintype "passive"))
      (node (ref "T5") (pin "1") (pinfunction "1_1") (pintype "bidirectional"))
    )
    (net (code "46") (name "Net-(D13-K)") (class "Default")
      (node (ref "C35") (pin "1") (pinfunction "1_1") (pintype "passive"))
      (node (ref "D13") (pin "C") (pinfunction "K_C") (pintype "bidirectional"))
      (node (ref "L11") (pin "1") (pinfunction "P$1_1") (pintype "bidirectional"))
      (node (ref "R53") (pin "2") (pinfunction "2_2") (pintype "passive"))
      (node (ref "T6") (pin "1") (pinfunction "1_1") (pintype "bidirectional"))
    )
    (net (code "47") (name "Net-(F1-P$1)") (class "Default")
      (node (ref "F1") (pin "1") (pinfunction "P$1_1") (pintype "bidirectional"))
      (node (ref "T1") (pin "2") (pinfunction "2_2") (pintype "bidirectional"))
    )
    (net (code "48") (name "Net-(F2-P$1)") (class "Default")
      (node (ref "F2") (pin "1") (pinfunction "P$1_1") (pintype "bidirectional"))
      (node (ref "T3") (pin "2") (pinfunction "2_2") (pintype "bidirectional"))
    )
    (net (code "49") (name "Net-(F3-P$1)") (class "Default")
      (node (ref "F3") (pin "1") (pinfunction "P$1_1") (pintype "bidirectional"))
      (node (ref "T5") (pin "2") (pinfunction "2_2") (pintype "bidirectional"))
    )
    (net (code "50") (name "Net-(F4-P$1)") (class "Default")
      (node (ref "F4") (pin "1") (pinfunction "P$1_1") (pintype "bidirectional"))
      (node (ref "T7") (pin "2") (pinfunction "2_2") (pintype "bidirectional"))
    )
    (net (code "51") (name "Net-(J4-V+)") (class "Default")
      (node (ref "CR1") (pin "A") (pinfunction "A_A") (pintype "bidirectional"))
      (node (ref "CR2") (pin "K") (pinfunction "K_K") (pintype "bidirectional"))
      (node (ref "J4") (pin "1") (pinfunction "V+_1") (pintype "bidirectional"))
    )
    (net (code "52") (name "Net-(J5-CLK)") (class "Default")
      (node (ref "J5") (pin "P5") (pinfunction "CLK_P5") (pintype "bidirectional"))
      (node (ref "R4") (pin "1") (pinfunction "1_1") (pintype "passive"))
    )
    (net (code "53") (name "Net-(J5-CMD{slash}MOSI)") (class "Default")
      (node (ref "J5") (pin "P3") (pinfunction "CMD/MOSI_P3") (pintype "bidirectional"))
      (node (ref "R2") (pin "1") (pinfunction "1_1") (pintype "passive"))
    )
    (net (code "54") (name "Net-(J5-DAT0{slash}MISO)") (class "Default")
      (node (ref "J5") (pin "P7") (pinfunction "DAT0/MISO_P7") (pintype "bidirectional"))
      (node (ref "R10") (pin "1") (pinfunction "1_1") (pintype "passive"))
    )
    (net (code "55") (name "Net-(J5-DAT3{slash}CS)") (class "Default")
      (node (ref "J5") (pin "P2") (pinfunction "DAT3/CS_P2") (pintype "bidirectional"))
      (node (ref "R1") (pin "1") (pinfunction "1_1") (pintype "passive"))
    )
    (net (code "56") (name "Net-(L1-P$2)") (class "Default")
      (node (ref "GDT1") (pin "L1") (pinfunction "L1_L1") (pintype "bidirectional"))
      (node (ref "J6") (pin "1L") (pinfunction "1L_1L") (pintype "bidirectional"))
      (node (ref "L1") (pin "2") (pinfunction "P$2_2") (pintype "bidirectional"))
    )
    (net (code "57") (name "Net-(L2-P$1)") (class "Default")
      (node (ref "C2") (pin "2") (pinfunction "2_2") (pintype "passive"))
      (node (ref "D3") (pin "A") (pinfunction "A_A") (pintype "bidirectional"))
      (node (ref "L2") (pin "1") (pinfunction "P$1_1") (pintype "bidirectional"))
      (node (ref "R5") (pin "1") (pinfunction "1_1") (pintype "passive"))
      (node (ref "T1") (pin "3") (pinfunction "3_3") (pintype "bidirectional"))
    )
    (net (code "58") (name "Net-(L2-P$2)") (class "Default")
      (node (ref "GDT1") (pin "L2") (pinfunction "L2_L2") (pintype "bidirectional"))
      (node (ref "J6") (pin "2L") (pinfunction "2L_2L") (pintype "bidirectional"))
      (node (ref "L2") (pin "2") (pinfunction "P$2_2") (pintype "bidirectional"))
    )
    (net (code "59") (name "Net-(L3-P$2)") (class "Default")
      (node (ref "GDT2") (pin "L1") (pinfunction "L1_L1") (pintype "bidirectional"))
      (node (ref "J6") (pin "1H") (pinfunction "1H_1H") (pintype "bidirectional"))
      (node (ref "L3") (pin "2") (pinfunction "P$2_2") (pintype "bidirectional"))
    )
    (net (code "60") (name "Net-(L4-P$1)") (class "Default")
      (node (ref "C3") (pin "2") (pinfunction "2_2") (pintype "passive"))
      (node (ref "D4") (pin "A") (pinfunction "A_A") (pintype "bidirectional"))
      (node (ref "L4") (pin "1") (pinfunction "P$1_1") (pintype "bidirectional"))
      (node (ref "R6") (pin "1") (pinfunction "1_1") (pintype "passive"))
      (node (ref "T2") (pin "3") (pinfunction "3_3") (pintype "bidirectional"))
    )
    (net (code "61") (name "Net-(L4-P$2)") (class "Default")
      (node (ref "GDT2") (pin "L2") (pinfunction "L2_L2") (pintype "bidirectional"))
      (node (ref "J6") (pin "2H") (pinfunction "2H_2H") (pintype "bidirectional"))
      (node (ref "L4") (pin "2") (pinfunction "P$2_2") (pintype "bidirectional"))
    )
    (net (code "62") (name "Net-(L5-P$2)") (class "Default")
      (node (ref "GDT3") (pin "L1") (pinfunction "L1_L1") (pintype "bidirectional"))
      (node (ref "J6") (pin "3L") (pinfunction "3L_3L") (pintype "bidirectional"))
      (node (ref "L5") (pin "2") (pinfunction "P$2_2") (pintype "bidirectional"))
    )
    (net (code "63") (name "Net-(L6-P$1)") (class "Default")
      (node (ref "C19") (pin "2") (pinfunction "2_2") (pintype "passive"))
      (node (ref "D8") (pin "A") (pinfunction "A_A") (pintype "bidirectional"))
      (node (ref "L6") (pin "1") (pinfunction "P$1_1") (pintype "bidirectional"))
      (node (ref "R32") (pin "1") (pinfunction "1_1") (pintype "passive"))
      (node (ref "T3") (pin "3") (pinfunction "3_3") (pintype "bidirectional"))
    )
    (net (code "64") (name "Net-(L6-P$2)") (class "Default")
      (node (ref "GDT3") (pin "L2") (pinfunction "L2_L2") (pintype "bidirectional"))
      (node (ref "J6") (pin "4L") (pinfunction "4L_4L") (pintype "bidirectional"))
      (node (ref "L6") (pin "2") (pinfunction "P$2_2") (pintype "bidirectional"))
    )
    (net (code "65") (name "Net-(L7-P$2)") (class "Default")
      (node (ref "GDT4") (pin "L1") (pinfunction "L1_L1") (pintype "bidirectional"))
      (node (ref "J6") (pin "3H") (pinfunction "3H_3H") (pintype "bidirectional"))
      (node (ref "L7") (pin "2") (pinfunction "P$2_2") (pintype "bidirectional"))
    )
    (net (code "66") (name "Net-(L8-P$1)") (class "Default")
      (node (ref "C20") (pin "2") (pinfunction "2_2") (pintype "passive"))
      (node (ref "D9") (pin "A") (pinfunction "A_A") (pintype "bidirectional"))
      (node (ref "L8") (pin "1") (pinfunction "P$1_1") (pintype "bidirectional"))
      (node (ref "R33") (pin "1") (pinfunction "1_1") (pintype "passive"))
      (node (ref "T4") (pin "3") (pinfunction "3_3") (pintype "bidirectional"))
    )
    (net (code "67") (name "Net-(L8-P$2)") (class "Default")
      (node (ref "GDT4") (pin "L2") (pinfunction "L2_L2") (pintype "bidirectional"))
      (node (ref "J6") (pin "4H") (pinfunction "4H_4H") (pintype "bidirectional"))
      (node (ref "L8") (pin "2") (pinfunction "P$2_2") (pintype "bidirectional"))
    )
    (net (code "68") (name "Net-(L9-P$2)") (class "Default")
      (node (ref "GDT5") (pin "L1") (pinfunction "L1_L1") (pintype "bidirectional"))
      (node (ref "J7") (pin "1L") (pinfunction "1L_1L") (pintype "bidirectional"))
      (node (ref "L9") (pin "2") (pinfunction "P$2_2") (pintype "bidirectional"))
    )
    (net (code "69") (name "Net-(L10-P$1)") (class "Default")
      (node (ref "C33") (pin "2") (pinfunction "2_2") (pintype "passive"))
      (node (ref "D12") (pin "A") (pinfunction "A_A") (pintype "bidirectional"))
      (node (ref "L10") (pin "1") (pinfunction "P$1_1") (pintype "bidirectional"))
      (node (ref "R52") (pin "1") (pinfunction "1_1") (pintype "passive"))
      (node (ref "T5") (pin "3") (pinfunction "3_3") (pintype "bidirectional"))
    )
    (net (code "70") (name "Net-(L10-P$2)") (class "Default")
      (node (ref "GDT5") (pin "L2") (pinfunction "L2_L2") (pintype "bidirectional"))
      (node (ref "J7") (pin "2L") (pinfunction "2L_2L") (pintype "bidirectional"))
      (node (ref "L10") (pin "2") (pinfunction "P$2_2") (pintype "bidirectional"))
    )
    (net (code "71") (name "Net-(L11-P$2)") (class "Default")
      (node (ref "GDT6") (pin "L1") (pinfunction "L1_L1") (pintype "bidirectional"))
      (node (ref "J7") (pin "1H") (pinfunction "1H_1H") (pintype "bidirectional"))
      (node (ref "L11") (pin "2") (pinfunction "P$2_2") (pintype "bidirectional"))
    )
    (net (code "72") (name "Net-(L12-P$1)") (class "Default")
      (node (ref "C34") (pin "2") (pinfunction "2_2") (pintype "passive"))
      (node (ref "D13") (pin "A") (pinfunction "A_A") (pintype "bidirectional"))
      (node (ref "L12") (pin "1") (pinfunction "P$1_1") (pintype "bidirectional"))
      (node (ref "R53") (pin "1") (pinfunction "1_1") (pintype "passive"))
      (node (ref "T6") (pin "3") (pinfunction "3_3") (pintype "bidirectional"))
    )
    (net (code "73") (name "Net-(L12-P$2)") (class "Default")
      (node (ref "GDT6") (pin "L2") (pinfunction "L2_L2") (pintype "bidirectional"))
      (node (ref "J7") (pin "2H") (pinfunction "2H_2H") (pintype "bidirectional"))
      (node (ref "L12") (pin "2") (pinfunction "P$2_2") (pintype "bidirectional"))
    )
    (net (code "74") (name "Net-(L13-P$2)") (class "Default")
      (node (ref "GDT7") (pin "L1") (pinfunction "L1_L1") (pintype "bidirectional"))
      (node (ref "J7") (pin "3L") (pinfunction "3L_3L") (pintype "bidirectional"))
      (node (ref "L13") (pin "2") (pinfunction "P$2_2") (pintype "bidirectional"))
    )
    (net (code "75") (name "Net-(L14-P$1)") (class "Default")
      (node (ref "C26") (pin "2") (pinfunction "2_2") (pintype "passive"))
      (node (ref "D10") (pin "A") (pinfunction "A_A") (pintype "bidirectional"))
      (node (ref "L14") (pin "1") (pinfunction "P$1_1") (pintype "bidirectional"))
      (node (ref "R42") (pin "1") (pinfunction "1_1") (pintype "passive"))
      (node (ref "T7") (pin "3") (pinfunction "3_3") (pintype "bidirectional"))
    )
    (net (code "76") (name "Net-(L14-P$2)") (class "Default")
      (node (ref "GDT7") (pin "L2") (pinfunction "L2_L2") (pintype "bidirectional"))
      (node (ref "J7") (pin "4L") (pinfunction "4L_4L") (pintype "bidirectional"))
      (node (ref "L14") (pin "2") (pinfunction "P$2_2") (pintype "bidirectional"))
    )
    (net (code "77") (name "Net-(L15-P$2)") (class "Default")
      (node (ref "GDT8") (pin "L1") (pinfunction "L1_L1") (pintype "bidirectional"))
      (node (ref "J7") (pin "3H") (pinfunction "3H_3H") (pintype "bidirectional"))
      (node (ref "L15") (pin "2") (pinfunction "P$2_2") (pintype "bidirectional"))
    )
    (net (code "78") (name "Net-(L16-P$1)") (class "Default")
      (node (ref "C27") (pin "2") (pinfunction "2_2") (pintype "passive"))
      (node (ref "D11") (pin "A") (pinfunction "A_A") (pintype "bidirectional"))
      (node (ref "L16") (pin "1") (pinfunction "P$1_1") (pintype "bidirectional"))
      (node (ref "R43") (pin "1") (pinfunction "1_1") (pintype "passive"))
      (node (ref "T8") (pin "3") (pinfunction "3_3") (pintype "bidirectional"))
    )
    (net (code "79") (name "Net-(L16-P$2)") (class "Default")
      (node (ref "GDT8") (pin "L2") (pinfunction "L2_L2") (pintype "bidirectional"))
      (node (ref "J7") (pin "4H") (pinfunction "4H_4H") (pintype "bidirectional"))
      (node (ref "L16") (pin "2") (pinfunction "P$2_2") (pintype "bidirectional"))
    )
    (net (code "80") (name "Net-(R7-Pad2)") (class "Default")
      (node (ref "R7") (pin "2") (pinfunction "2_2") (pintype "passive"))
      (node (ref "T2") (pin "2") (pinfunction "2_2") (pintype "bidirectional"))
    )
    (net (code "81") (name "Net-(R34-Pad2)") (class "Default")
      (node (ref "R34") (pin "2") (pinfunction "2_2") (pintype "passive"))
      (node (ref "T4") (pin "2") (pinfunction "2_2") (pintype "bidirectional"))
    )
    (net (code "82") (name "Net-(R44-Pad2)") (class "Default")
      (node (ref "R44") (pin "2") (pinfunction "2_2") (pintype "passive"))
      (node (ref "T8") (pin "2") (pinfunction "2_2") (pintype "bidirectional"))
    )
    (net (code "83") (name "Net-(R54-Pad2)") (class "Default")
      (node (ref "R54") (pin "2") (pinfunction "2_2") (pintype "passive"))
      (node (ref "T6") (pin "2") (pinfunction "2_2") (pintype "bidirectional"))
    )
    (net (code "84") (name "Net-(SW1-2)") (class "Default")
      (node (ref "R16") (pin "2") (pinfunction "2_2") (pintype "passive"))
      (node (ref "R27") (pin "2") (pinfunction "2_2") (pintype "passive"))
      (node (ref "SW1") (pin "S2") (pinfunction "2_S2") (pintype "passive"))
    )
    (net (code "85") (name "Net-(U1-A)") (class "Default")
      (node (ref "C22") (pin "2") (pinfunction "2_2") (pintype "passive"))
      (node (ref "R41") (pin "1") (pinfunction "1_1") (pintype "passive"))
      (node (ref "T4") (pin "4") (pinfunction "4_4") (pintype "bidirectional"))
      (node (ref "U1") (pin "8") (pinfunction "A_8") (pintype "bidirectional"))
    )
    (net (code "86") (name "Net-(U1-B)") (class "Default")
      (node (ref "C22") (pin "1") (pinfunction "1_1") (pintype "passive"))
      (node (ref "R41") (pin "2") (pinfunction "2_2") (pintype "passive"))
      (node (ref "T4") (pin "6") (pinfunction "6_6") (pintype "bidirectional"))
      (node (ref "U1") (pin "7") (pinfunction "B_7") (pintype "bidirectional"))
    )
    (net (code "87") (name "Net-(U1-Y)") (class "Default")
      (node (ref "R37") (pin "1") (pinfunction "1_1") (pintype "passive"))
      (node (ref "U1") (pin "5") (pinfunction "Y_5") (pintype "bidirectional"))
    )
    (net (code "88") (name "Net-(U1-Z)") (class "Default")
      (node (ref "R38") (pin "1") (pinfunction "1_1") (pintype "passive"))
      (node (ref "U1") (pin "6") (pinfunction "Z_6") (pintype "bidirectional"))
    )
    (net (code "89") (name "Net-(U2-A)") (class "Default")
      (node (ref "C36") (pin "2") (pinfunction "2_2") (pintype "passive"))
      (node (ref "R61") (pin "1") (pinfunction "1_1") (pintype "passive"))
      (node (ref "T6") (pin "4") (pinfunction "4_4") (pintype "bidirectional"))
      (node (ref "U2") (pin "8") (pinfunction "A_8") (pintype "bidirectional"))
    )
    (net (code "90") (name "Net-(U2-B)") (class "Default")
      (node (ref "C36") (pin "1") (pinfunction "1_1") (pintype "passive"))
      (node (ref "R61") (pin "2") (pinfunction "2_2") (pintype "passive"))
      (node (ref "T6") (pin "6") (pinfunction "6_6") (pintype "bidirectional"))
      (node (ref "U2") (pin "7") (pinfunction "B_7") (pintype "bidirectional"))
    )
    (net (code "91") (name "Net-(U2-Y)") (class "Default")
      (node (ref "R57") (pin "1") (pinfunction "1_1") (pintype "passive"))
      (node (ref "U2") (pin "5") (pinfunction "Y_5") (pintype "bidirectional"))
    )
    (net (code "92") (name "Net-(U2-Z)") (class "Default")
      (node (ref "R58") (pin "1") (pinfunction "1_1") (pintype "passive"))
      (node (ref "U2") (pin "6") (pinfunction "Z_6") (pintype "bidirectional"))
    )
    (net (code "93") (name "Net-(U3-A)") (class "Default")
      (node (ref "C7") (pin "2") (pinfunction "2_2") (pintype "passive"))
      (node (ref "R14") (pin "1") (pinfunction "1_1") (pintype "passive"))
      (node (ref "T2") (pin "4") (pinfunction "4_4") (pintype "bidirectional"))
      (node (ref "U3") (pin "8") (pinfunction "A_8") (pintype "bidirectional"))
    )
    (net (code "94") (name "Net-(U3-B)") (class "Default")
      (node (ref "C7") (pin "1") (pinfunction "1_1") (pintype "passive"))
      (node (ref "R14") (pin "2") (pinfunction "2_2") (pintype "passive"))
      (node (ref "T2") (pin "6") (pinfunction "6_6") (pintype "bidirectional"))
      (node (ref "U3") (pin "7") (pinfunction "B_7") (pintype "bidirectional"))
    )
    (net (code "95") (name "Net-(U3-Y)") (class "Default")
      (node (ref "R12") (pin "1") (pinfunction "1_1") (pintype "passive"))
      (node (ref "U3") (pin "5") (pinfunction "Y_5") (pintype "bidirectional"))
    )
    (net (code "96") (name "Net-(U3-Z)") (class "Default")
      (node (ref "R13") (pin "1") (pinfunction "1_1") (pintype "passive"))
      (node (ref "U3") (pin "6") (pinfunction "Z_6") (pintype "bidirectional"))
    )
    (net (code "97") (name "Net-(U5-A)") (class "Default")
      (node (ref "C29") (pin "2") (pinfunction "2_2") (pintype "passive"))
      (node (ref "R51") (pin "1") (pinfunction "1_1") (pintype "passive"))
      (node (ref "T8") (pin "4") (pinfunction "4_4") (pintype "bidirectional"))
      (node (ref "U5") (pin "8") (pinfunction "A_8") (pintype "bidirectional"))
    )
    (net (code "98") (name "Net-(U5-B)") (class "Default")
      (node (ref "C29") (pin "1") (pinfunction "1_1") (pintype "passive"))
      (node (ref "R51") (pin "2") (pinfunction "2_2") (pintype "passive"))
      (node (ref "T8") (pin "6") (pinfunction "6_6") (pintype "bidirectional"))
      (node (ref "U5") (pin "7") (pinfunction "B_7") (pintype "bidirectional"))
    )
    (net (code "99") (name "Net-(U5-Y)") (class "Default")
      (node (ref "R47") (pin "1") (pinfunction "1_1") (pintype "passive"))
      (node (ref "U5") (pin "5") (pinfunction "Y_5") (pintype "bidirectional"))
    )
    (net (code "100") (name "Net-(U5-Z)") (class "Default")
      (node (ref "R48") (pin "1") (pinfunction "1_1") (pintype "passive"))
      (node (ref "U5") (pin "6") (pinfunction "Z_6") (pintype "bidirectional"))
    )
    (net (code "101") (name "Net-(U7-GP16)") (class "Default")
      (node (ref "R24") (pin "2") (pinfunction "2_2") (pintype "passive"))
      (node (ref "U7") (pin "21") (pinfunction "GP16_21") (pintype "bidirectional"))
    )
    (net (code "102") (name "Net-(U7-GP17)") (class "Default")
      (node (ref "R23") (pin "2") (pinfunction "2_2") (pintype "passive"))
      (node (ref "U7") (pin "22") (pinfunction "GP17_22") (pintype "bidirectional"))
    )
    (net (code "103") (name "Net-(U7-GP18)") (class "Default")
      (node (ref "R25") (pin "2") (pinfunction "2_2") (pintype "passive"))
      (node (ref "U7") (pin "24") (pinfunction "GP18_24") (pintype "bidirectional"))
    )
    (net (code "104") (name "Net-(U7-GP19)") (class "Default")
      (node (ref "R22") (pin "2") (pinfunction "2_2") (pintype "passive"))
      (node (ref "U7") (pin "25") (pinfunction "GP19_25") (pintype "bidirectional"))
    )
    (net (code "105") (name "Net-(U7-GP20)") (class "Default")
      (node (ref "R26") (pin "2") (pinfunction "2_2") (pintype "passive"))
      (node (ref "U7") (pin "26") (pinfunction "GP20_26") (pintype "bidirectional"))
    )
    (net (code "106") (name "Net-(U7-GP21)") (class "Default")
      (node (ref "R21") (pin "2") (pinfunction "2_2") (pintype "passive"))
      (node (ref "U7") (pin "27") (pinfunction "GP21_27") (pintype "bidirectional"))
    )
    (net (code "107") (name "Net-(U7-GP26)") (class "Default")
      (node (ref "R20") (pin "2") (pinfunction "2_2") (pintype "passive"))
      (node (ref "U7") (pin "31") (pinfunction "GP26_31") (pintype "bidirectional"))
    )
    (net (code "108") (name "Net-(U7-GP27)") (class "Default")
      (node (ref "R17") (pin "2") (pinfunction "2_2") (pintype "passive"))
      (node (ref "U7") (pin "32") (pinfunction "GP27_32") (pintype "bidirectional"))
    )
    (net (code "109") (name "PE") (class "Default")
      (node (ref "C10") (pin "2") (pinfunction "2_2") (pintype "passive"))
      (node (ref "C16") (pin "2") (pinfunction "2_2") (pintype "passive"))
      (node (ref "C18") (pin "2") (pinfunction "2_2") (pintype "passive"))
      (node (ref "C19") (pin "1") (pinfunction "1_1") (pintype "passive"))
      (node (ref "C2") (pin "1") (pinfunction "1_1") (pintype "passive"))
      (node (ref "C20") (pin "1") (pinfunction "1_1") (pintype "passive"))
      (node (ref "C21") (pin "2") (pinfunction "2_2") (pintype "passive"))
      (node (ref "C25") (pin "2") (pinfunction "2_2") (pintype "passive"))
      (node (ref "C26") (pin "1") (pinfunction "1_1") (pintype "passive"))
      (node (ref "C27") (pin "1") (pinfunction "1_1") (pintype "passive"))
      (node (ref "C28") (pin "2") (pinfunction "2_2") (pintype "passive"))
      (node (ref "C3") (pin "1") (pinfunction "1_1") (pintype "passive"))
      (node (ref "C32") (pin "2") (pinfunction "2_2") (pintype "passive"))
      (node (ref "C33") (pin "1") (pinfunction "1_1") (pintype "passive"))
      (node (ref "C34") (pin "1") (pinfunction "1_1") (pintype "passive"))
      (node (ref "C35") (pin "2") (pinfunction "2_2") (pintype "passive"))
      (node (ref "C38") (pin "2") (pinfunction "2_2") (pintype "passive"))
      (node (ref "C39") (pin "2") (pinfunction "2_2") (pintype "passive"))
      (node (ref "C4") (pin "2") (pinfunction "2_2") (pintype "passive"))
      (node (ref "C40") (pin "2") (pinfunction "2_2") (pintype "passive"))
      (node (ref "CR2") (pin "A") (pinfunction "A_A") (pintype "bidirectional"))
      (node (ref "GDT1") (pin "C") (pinfunction "C_C") (pintype "bidirectional"))
      (node (ref "GDT2") (pin "C") (pinfunction "C_C") (pintype "bidirectional"))
      (node (ref "GDT3") (pin "C") (pinfunction "C_C") (pintype "bidirectional"))
      (node (ref "GDT4") (pin "C") (pinfunction "C_C") (pintype "bidirectional"))
      (node (ref "GDT5") (pin "C") (pinfunction "C_C") (pintype "bidirectional"))
      (node (ref "GDT6") (pin "C") (pinfunction "C_C") (pintype "bidirectional"))
      (node (ref "GDT7") (pin "C") (pinfunction "C_C") (pintype "bidirectional"))
      (node (ref "GDT8") (pin "C") (pinfunction "C_C") (pintype "bidirectional"))
      (node (ref "J3") (pin "P$1") (pinfunction "P$1_P$1") (pintype "bidirectional"))
      (node (ref "J3") (pin "P$2") (pinfunction "P$2_P$2") (pintype "bidirectional"))
      (node (ref "J3") (pin "P$3") (pinfunction "P$3_P$3") (pintype "bidirectional"))
      (node (ref "J3") (pin "P$4") (pinfunction "P$4_P$4") (pintype "bidirectional"))
      (node (ref "J4") (pin "2") (pinfunction "GND_2") (pintype "bidirectional"))
      (node (ref "R34") (pin "1") (pinfunction "1_1") (pintype "passive"))
      (node (ref "R44") (pin "1") (pinfunction "1_1") (pintype "passive"))
      (node (ref "R54") (pin "1") (pinfunction "1_1") (pintype "passive"))
      (node (ref "R7") (pin "1") (pinfunction "1_1") (pintype "passive"))
      (node (ref "R8") (pin "2") (pinfunction "2_2") (pintype "passive"))
    )
    (net (code "110") (name "SWGND") (class "Default")
      (node (ref "U7") (pin "42") (pinfunction "SWGND_42") (pintype "power_in"))
    )
    (net (code "111") (name "V+") (class "Default")
      (node (ref "CR1") (pin "K") (pinfunction "K_K") (pintype "bidirectional"))
      (node (ref "F1") (pin "2") (pinfunction "P$2_2") (pintype "bidirectional"))
      (node (ref "F2") (pin "2") (pinfunction "P$2_2") (pintype "bidirectional"))
      (node (ref "F3") (pin "2") (pinfunction "P$2_2") (pintype "bidirectional"))
      (node (ref "F4") (pin "2") (pinfunction "P$2_2") (pintype "bidirectional"))
      (node (ref "R29") (pin "2") (pinfunction "2_2") (pintype "passive"))
    )
    (net (code "112") (name "VBUS") (class "Default")
      (node (ref "U7") (pin "40") (pinfunction "VBUS_40") (pintype "power_in"))
    )
    (net (code "113") (name "VMID") (class "Default")
      (node (ref "C1") (pin "1") (pinfunction "1_1") (pintype "passive"))
      (node (ref "C17") (pin "1") (pinfunction "1_1") (pintype "passive"))
      (node (ref "C24") (pin "1") (pinfunction "1_1") (pintype "passive"))
      (node (ref "C31") (pin "1") (pinfunction "1_1") (pintype "passive"))
      (node (ref "R18") (pin "1") (pinfunction "1_1") (pintype "passive"))
      (node (ref "R19") (pin "2") (pinfunction "2_2") (pintype "passive"))
      (node (ref "T2") (pin "5") (pinfunction "5_5") (pintype "bidirectional"))
      (node (ref "T4") (pin "5") (pinfunction "5_5") (pintype "bidirectional"))
      (node (ref "T6") (pin "5") (pinfunction "5_5") (pintype "bidirectional"))
      (node (ref "T8") (pin "5") (pinfunction "5_5") (pintype "bidirectional"))
    )
    (net (code "114") (name "VSYS") (class "Default")
      (node (ref "U7") (pin "39") (pinfunction "VSYS_39") (pintype "power_in"))
    )
    (net (code "115") (name "unconnected-(J4-NO-Pad3)") (class "Default")
      (node (ref "J4") (pin "3") (pinfunction "NO_3") (pintype "bidirectional"))
    )
    (net (code "116") (name "unconnected-(J5-DAT1-PadP8)") (class "Default")
      (node (ref "J5") (pin "P8") (pinfunction "DAT1_P8") (pintype "bidirectional"))
    )
    (net (code "117") (name "unconnected-(J5-DAT2-PadP1)") (class "Default")
      (node (ref "J5") (pin "P1") (pinfunction "DAT2_P1") (pintype "bidirectional"))
    )
    (net (code "118") (name "unconnected-(T1-Pad5)") (class "Default")
      (node (ref "T1") (pin "5") (pinfunction "5_5") (pintype "bidirectional"))
    )
    (net (code "119") (name "unconnected-(T3-Pad5)") (class "Default")
      (node (ref "T3") (pin "5") (pinfunction "5_5") (pintype "bidirectional"))
    )
    (net (code "120") (name "unconnected-(T5-Pad5)") (class "Default")
      (node (ref "T5") (pin "5") (pinfunction "5_5") (pintype "bidirectional"))
    )
    (net (code "121") (name "unconnected-(T7-Pad5)") (class "Default")
      (node (ref "T7") (pin "5") (pinfunction "5_5") (pintype "bidirectional"))
    )
    (net (code "122") (name "unconnected-(U7-3V3_EN-Pad37)") (class "Default")
      (node (ref "U7") (pin "37") (pinfunction "3V3_EN_37") (pintype "input"))
    )
    (net (code "123") (name "unconnected-(U7-ADC_REF-Pad35)") (class "Default")
      (node (ref "U7") (pin "35") (pinfunction "ADC_REF_35") (pintype "input"))
    )
    (net (code "124") (name "unconnected-(U7-RUN-Pad30)") (class "Default")
      (node (ref "U7") (pin "30") (pinfunction "RUN_30") (pintype "input"))
    )
    (net (code "125") (name "unconnected-(U7-SWCLK-Pad41)") (class "Default")
      (node (ref "U7") (pin "41") (pinfunction "SWCLK_41") (pintype "input"))
    )
    (net (code "126") (name "unconnected-(U7-SWDIO-Pad43)") (class "Default")
      (node (ref "U7") (pin "43") (pinfunction "SWDIO_43") (pintype "bidirectional"))
    )
  )
)
